# ble_emg_recorder_v11.net
KiCad netlist of a schematic drawn in EAGLE
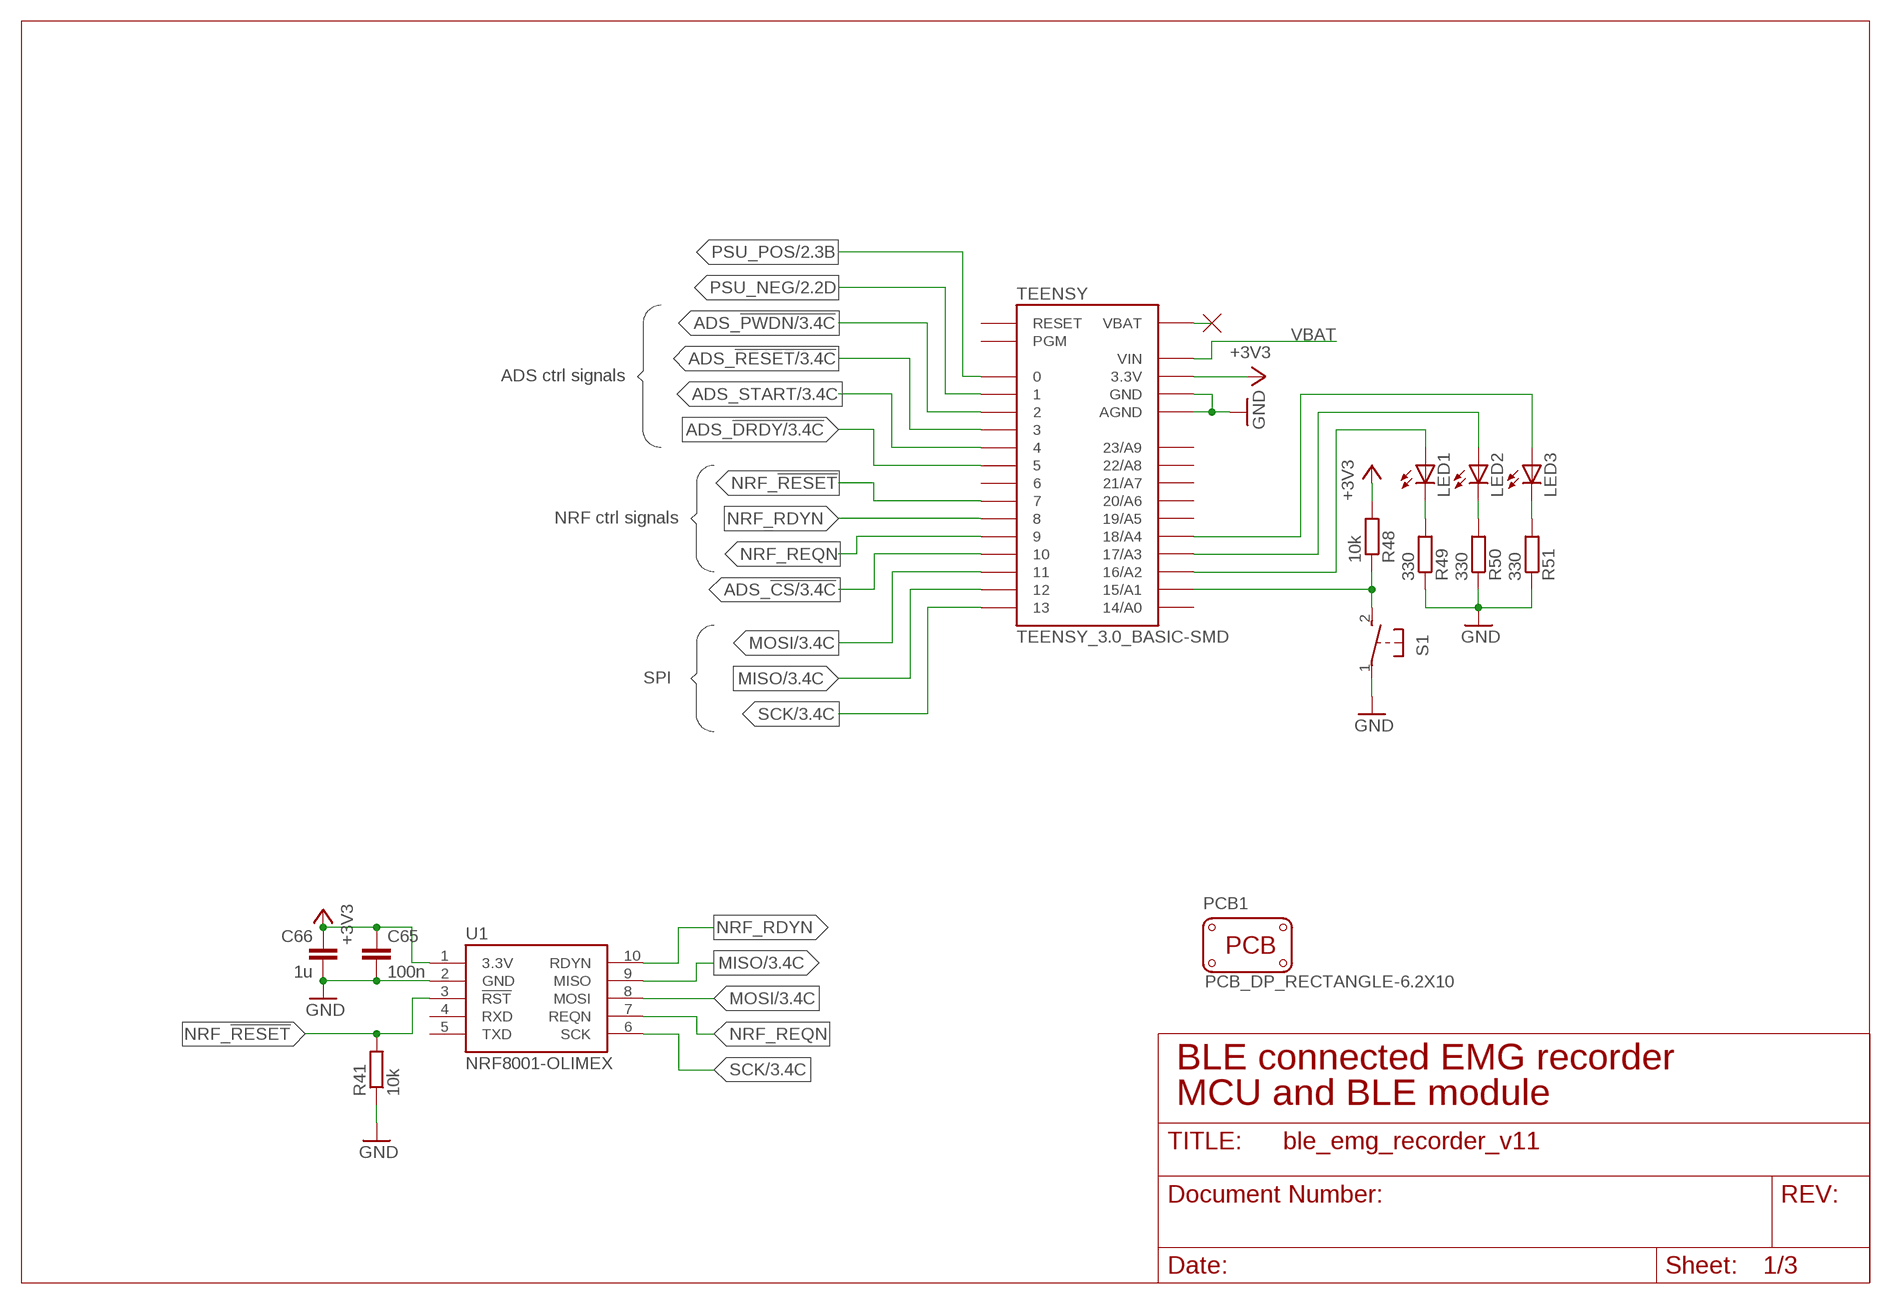
[diagram p0: schematic, sheet 1]
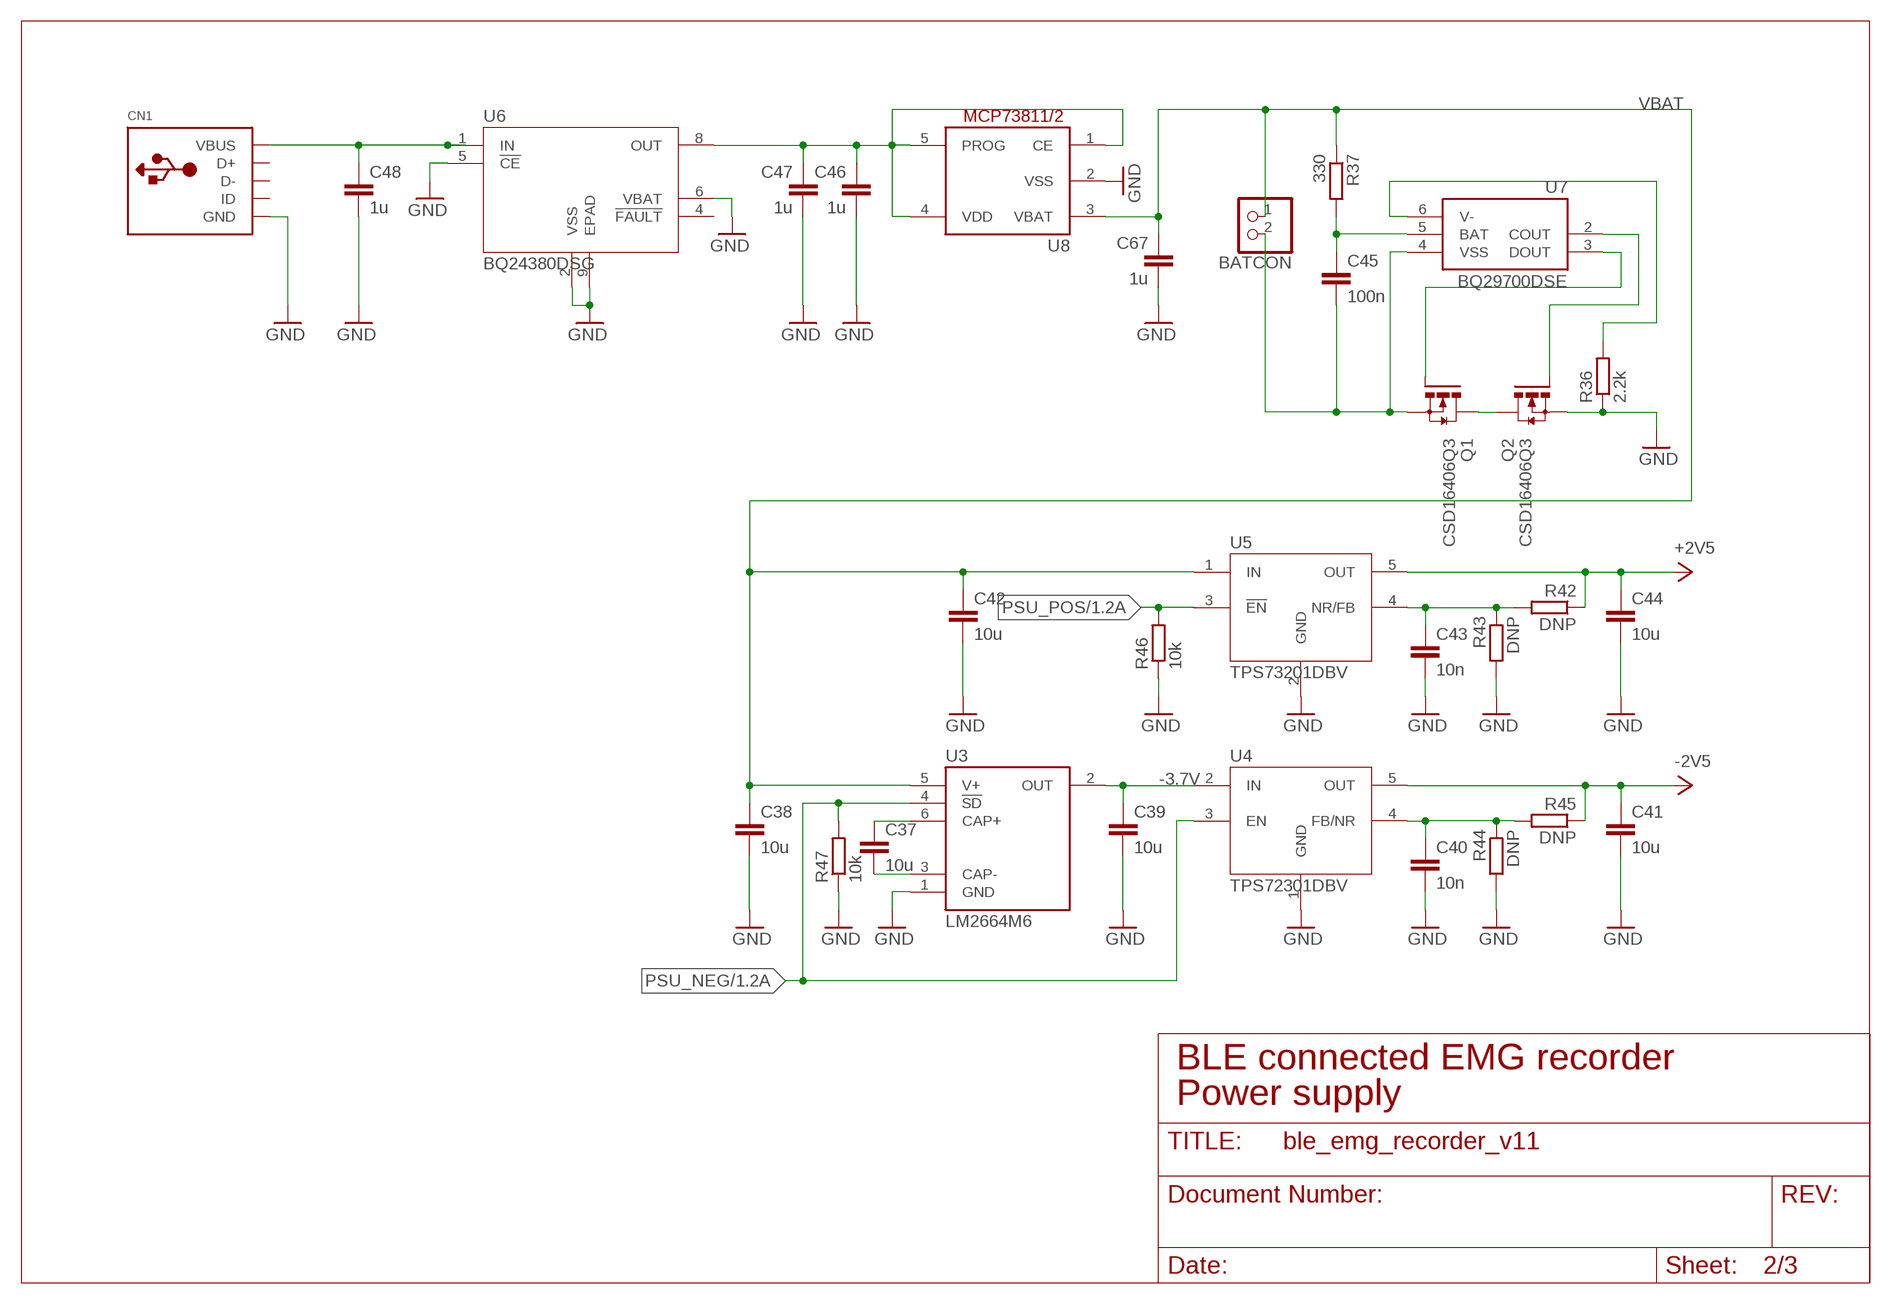
[diagram p1: schematic, sheet 2]
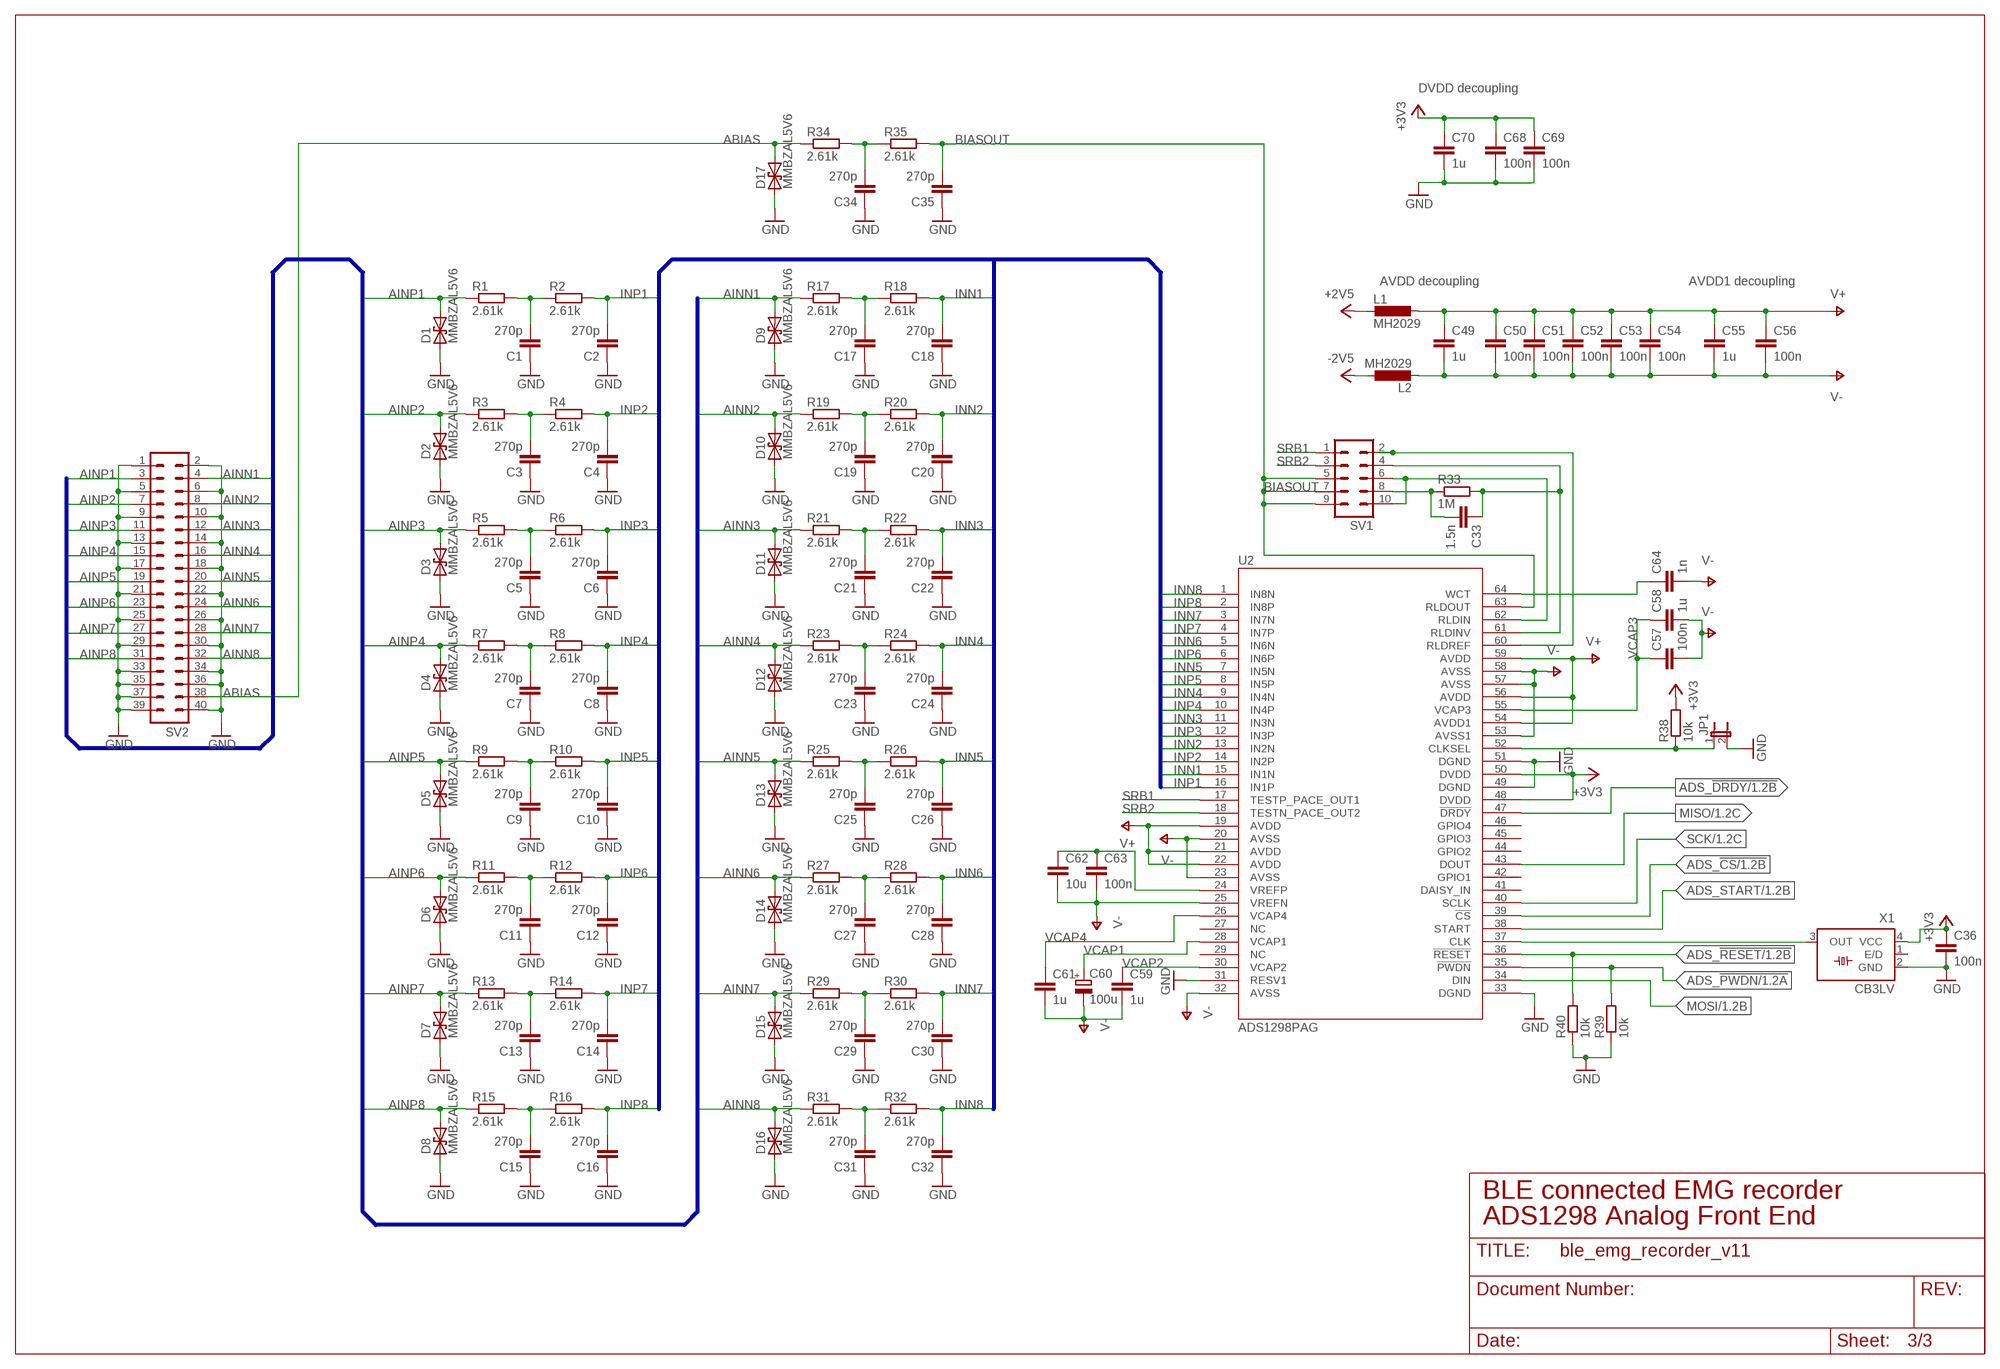
[diagram p2: schematic, sheet 3]

(export (version "E")
  (design (tool "Eeschema 10.0.6"))
  (components
    (comp (ref "C65")
      (value "100n")
      (footprint "eagle-import:C0805")
      (libsource (lib "eagle-import") (part "C-EUC0805"))
    )
    (comp (ref "C66")
      (value "1u")
      (footprint "eagle-import:C0805")
      (libsource (lib "eagle-import") (part "C-EUC0805"))
    )
    (comp (ref "LED1")
      (value "LEDCHIPLED_0805")
      (footprint "eagle-import:CHIPLED_0805")
      (libsource (lib "eagle-import") (part "LEDCHIPLED_0805"))
    )
    (comp (ref "LED2")
      (value "LEDCHIPLED_0805")
      (footprint "eagle-import:CHIPLED_0805")
      (libsource (lib "eagle-import") (part "LEDCHIPLED_0805"))
    )
    (comp (ref "LED3")
      (value "LEDCHIPLED_0805")
      (footprint "eagle-import:CHIPLED_0805")
      (libsource (lib "eagle-import") (part "LEDCHIPLED_0805"))
    )
    (comp (ref "PCB1")
      (value "PCB_DP_RECTANGLE-6.2X10")
      (footprint "eagle-import:DP10062_V1")
      (libsource (lib "eagle-import") (part "PCB_DP_RECTANGLE-6.2X10"))
    )
    (comp (ref "R41")
      (value "10k")
      (footprint "eagle-import:R0805")
      (libsource (lib "eagle-import") (part "R-EU_R0805"))
    )
    (comp (ref "R48")
      (value "10k")
      (footprint "eagle-import:R0805")
      (libsource (lib "eagle-import") (part "R-EU_R0805"))
    )
    (comp (ref "R49")
      (value "330")
      (footprint "eagle-import:R0805")
      (libsource (lib "eagle-import") (part "R-EU_R0805"))
    )
    (comp (ref "R50")
      (value "330")
      (footprint "eagle-import:R0805")
      (libsource (lib "eagle-import") (part "R-EU_R0805"))
    )
    (comp (ref "R51")
      (value "330")
      (footprint "eagle-import:R0805")
      (libsource (lib "eagle-import") (part "R-EU_R0805"))
    )
    (comp (ref "S1")
      (value "31-XX")
      (footprint "eagle-import:B3F-31XX")
      (fields (field (name "MPN") "B3F-3100"))
      (libsource (lib "eagle-import") (part "31-XX"))
    )
    (comp (ref "TEENSY")
      (value "TEENSY_3.0_BASIC-SMD")
      (footprint "eagle-import:TEENSY_3.0_BASIC-SMD")
      (libsource (lib "eagle-import") (part "TEENSY_3.0_BASIC-?SMD"))
    )
    (comp (ref "U1")
      (value "NRF8001-OLIMEX")
      (footprint "eagle-import:NRF8001-OLIMEX")
      (libsource (lib "eagle-import") (part "NRF8001-OLIMEX"))
    )
    (comp (ref "C1")
      (value "270p")
      (footprint "eagle-import:C0805")
      (libsource (lib "eagle-import") (part "C-EUC0805"))
    )
    (comp (ref "C2")
      (value "270p")
      (footprint "eagle-import:C0805")
      (fields (field (name "DIGIKEY") "1276-2494-1-ND"))
      (libsource (lib "eagle-import") (part "C-EUC0805"))
    )
    (comp (ref "C3")
      (value "270p")
      (footprint "eagle-import:C0805")
      (fields (field (name "DIGIKEY") "1276-2494-1-ND"))
      (libsource (lib "eagle-import") (part "C-EUC0805"))
    )
    (comp (ref "C4")
      (value "270p")
      (footprint "eagle-import:C0805")
      (fields (field (name "DIGIKEY") "1276-2494-1-ND"))
      (libsource (lib "eagle-import") (part "C-EUC0805"))
    )
    (comp (ref "C5")
      (value "270p")
      (footprint "eagle-import:C0805")
      (fields (field (name "DIGIKEY") "1276-2494-1-ND"))
      (libsource (lib "eagle-import") (part "C-EUC0805"))
    )
    (comp (ref "C6")
      (value "270p")
      (footprint "eagle-import:C0805")
      (fields (field (name "DIGIKEY") "1276-2494-1-ND"))
      (libsource (lib "eagle-import") (part "C-EUC0805"))
    )
    (comp (ref "C7")
      (value "270p")
      (footprint "eagle-import:C0805")
      (fields (field (name "DIGIKEY") "1276-2494-1-ND"))
      (libsource (lib "eagle-import") (part "C-EUC0805"))
    )
    (comp (ref "C8")
      (value "270p")
      (footprint "eagle-import:C0805")
      (fields (field (name "DIGIKEY") "1276-2494-1-ND"))
      (libsource (lib "eagle-import") (part "C-EUC0805"))
    )
    (comp (ref "C9")
      (value "270p")
      (footprint "eagle-import:C0805")
      (fields (field (name "DIGIKEY") "1276-2494-1-ND"))
      (libsource (lib "eagle-import") (part "C-EUC0805"))
    )
    (comp (ref "C10")
      (value "270p")
      (footprint "eagle-import:C0805")
      (fields (field (name "DIGIKEY") "1276-2494-1-ND"))
      (libsource (lib "eagle-import") (part "C-EUC0805"))
    )
    (comp (ref "C11")
      (value "270p")
      (footprint "eagle-import:C0805")
      (fields (field (name "DIGIKEY") "1276-2494-1-ND"))
      (libsource (lib "eagle-import") (part "C-EUC0805"))
    )
    (comp (ref "C12")
      (value "270p")
      (footprint "eagle-import:C0805")
      (fields (field (name "DIGIKEY") "1276-2494-1-ND"))
      (libsource (lib "eagle-import") (part "C-EUC0805"))
    )
    (comp (ref "C13")
      (value "270p")
      (footprint "eagle-import:C0805")
      (fields (field (name "DIGIKEY") "1276-2494-1-ND"))
      (libsource (lib "eagle-import") (part "C-EUC0805"))
    )
    (comp (ref "C14")
      (value "270p")
      (footprint "eagle-import:C0805")
      (fields (field (name "DIGIKEY") "1276-2494-1-ND"))
      (libsource (lib "eagle-import") (part "C-EUC0805"))
    )
    (comp (ref "C15")
      (value "270p")
      (footprint "eagle-import:C0805")
      (fields (field (name "DIGIKEY") "1276-2494-1-ND"))
      (libsource (lib "eagle-import") (part "C-EUC0805"))
    )
    (comp (ref "C16")
      (value "270p")
      (footprint "eagle-import:C0805")
      (fields (field (name "DIGIKEY") "1276-2494-1-ND"))
      (libsource (lib "eagle-import") (part "C-EUC0805"))
    )
    (comp (ref "C17")
      (value "270p")
      (footprint "eagle-import:C0805")
      (fields (field (name "DIGIKEY") "1276-2494-1-ND"))
      (libsource (lib "eagle-import") (part "C-EUC0805"))
    )
    (comp (ref "C18")
      (value "270p")
      (footprint "eagle-import:C0805")
      (fields (field (name "DIGIKEY") "1276-2494-1-ND"))
      (libsource (lib "eagle-import") (part "C-EUC0805"))
    )
    (comp (ref "C19")
      (value "270p")
      (footprint "eagle-import:C0805")
      (fields (field (name "DIGIKEY") "1276-2494-1-ND"))
      (libsource (lib "eagle-import") (part "C-EUC0805"))
    )
    (comp (ref "C20")
      (value "270p")
      (footprint "eagle-import:C0805")
      (fields (field (name "DIGIKEY") "1276-2494-1-ND"))
      (libsource (lib "eagle-import") (part "C-EUC0805"))
    )
    (comp (ref "C21")
      (value "270p")
      (footprint "eagle-import:C0805")
      (fields (field (name "DIGIKEY") "1276-2494-1-ND"))
      (libsource (lib "eagle-import") (part "C-EUC0805"))
    )
    (comp (ref "C22")
      (value "270p")
      (footprint "eagle-import:C0805")
      (fields (field (name "DIGIKEY") "1276-2494-1-ND"))
      (libsource (lib "eagle-import") (part "C-EUC0805"))
    )
    (comp (ref "C23")
      (value "270p")
      (footprint "eagle-import:C0805")
      (fields (field (name "DIGIKEY") "1276-2494-1-ND"))
      (libsource (lib "eagle-import") (part "C-EUC0805"))
    )
    (comp (ref "C24")
      (value "270p")
      (footprint "eagle-import:C0805")
      (fields (field (name "DIGIKEY") "1276-2494-1-ND"))
      (libsource (lib "eagle-import") (part "C-EUC0805"))
    )
    (comp (ref "C25")
      (value "270p")
      (footprint "eagle-import:C0805")
      (fields (field (name "DIGIKEY") "1276-2494-1-ND"))
      (libsource (lib "eagle-import") (part "C-EUC0805"))
    )
    (comp (ref "C26")
      (value "270p")
      (footprint "eagle-import:C0805")
      (fields (field (name "DIGIKEY") "1276-2494-1-ND"))
      (libsource (lib "eagle-import") (part "C-EUC0805"))
    )
    (comp (ref "C27")
      (value "270p")
      (footprint "eagle-import:C0805")
      (fields (field (name "DIGIKEY") "1276-2494-1-ND"))
      (libsource (lib "eagle-import") (part "C-EUC0805"))
    )
    (comp (ref "C28")
      (value "270p")
      (footprint "eagle-import:C0805")
      (fields (field (name "DIGIKEY") "1276-2494-1-ND"))
      (libsource (lib "eagle-import") (part "C-EUC0805"))
    )
    (comp (ref "C29")
      (value "270p")
      (footprint "eagle-import:C0805")
      (fields (field (name "DIGIKEY") "1276-2494-1-ND"))
      (libsource (lib "eagle-import") (part "C-EUC0805"))
    )
    (comp (ref "C30")
      (value "270p")
      (footprint "eagle-import:C0805")
      (fields (field (name "DIGIKEY") "1276-2494-1-ND"))
      (libsource (lib "eagle-import") (part "C-EUC0805"))
    )
    (comp (ref "C31")
      (value "270p")
      (footprint "eagle-import:C0805")
      (fields (field (name "DIGIKEY") "1276-2494-1-ND"))
      (libsource (lib "eagle-import") (part "C-EUC0805"))
    )
    (comp (ref "C32")
      (value "270p")
      (footprint "eagle-import:C0805")
      (fields (field (name "DIGIKEY") "1276-2494-1-ND"))
      (libsource (lib "eagle-import") (part "C-EUC0805"))
    )
    (comp (ref "C33")
      (value "1.5n")
      (footprint "eagle-import:C0805")
      (libsource (lib "eagle-import") (part "C-EUC0805"))
    )
    (comp (ref "C34")
      (value "270p")
      (footprint "eagle-import:C0805")
      (fields (field (name "DIGIKEY") "1276-2494-1-ND"))
      (libsource (lib "eagle-import") (part "C-EUC0805"))
    )
    (comp (ref "C35")
      (value "270p")
      (footprint "eagle-import:C0805")
      (fields (field (name "DIGIKEY") "1276-2494-1-ND"))
      (libsource (lib "eagle-import") (part "C-EUC0805"))
    )
    (comp (ref "C36")
      (value "100n")
      (footprint "eagle-import:C0805")
      (libsource (lib "eagle-import") (part "C-EUC0805"))
    )
    (comp (ref "C49")
      (value "1u")
      (footprint "eagle-import:C0805")
      (libsource (lib "eagle-import") (part "C-EUC0805"))
    )
    (comp (ref "C50")
      (value "100n")
      (footprint "eagle-import:C0402")
      (libsource (lib "eagle-import") (part "C-EUC0402"))
    )
    (comp (ref "C51")
      (value "100n")
      (footprint "eagle-import:C0402")
      (libsource (lib "eagle-import") (part "C-EUC0402"))
    )
    (comp (ref "C52")
      (value "100n")
      (footprint "eagle-import:C0402")
      (libsource (lib "eagle-import") (part "C-EUC0402"))
    )
    (comp (ref "C53")
      (value "100n")
      (footprint "eagle-import:C0402")
      (libsource (lib "eagle-import") (part "C-EUC0402"))
    )
    (comp (ref "C54")
      (value "100n")
      (footprint "eagle-import:C0402")
      (libsource (lib "eagle-import") (part "C-EUC0402"))
    )
    (comp (ref "C55")
      (value "1u")
      (footprint "eagle-import:C0805")
      (libsource (lib "eagle-import") (part "C-EUC0805"))
    )
    (comp (ref "C56")
      (value "100n")
      (footprint "eagle-import:C0402")
      (libsource (lib "eagle-import") (part "C-EUC0402"))
    )
    (comp (ref "C57")
      (value "100n")
      (footprint "eagle-import:C0402")
      (libsource (lib "eagle-import") (part "C-EUC0402"))
    )
    (comp (ref "C58")
      (value "1u")
      (footprint "eagle-import:C0805")
      (libsource (lib "eagle-import") (part "C-EUC0805"))
    )
    (comp (ref "C59")
      (value "1u")
      (footprint "eagle-import:C0805")
      (libsource (lib "eagle-import") (part "C-EUC0805"))
    )
    (comp (ref "C60")
      (value "100u")
      (footprint "eagle-import:D_7343-31W")
      (libsource (lib "eagle-import") (part "CPOL-EUD/7343-31W"))
    )
    (comp (ref "C61")
      (value "1u")
      (footprint "eagle-import:C0805")
      (libsource (lib "eagle-import") (part "C-EUC0805"))
    )
    (comp (ref "C62")
      (value "10u")
      (footprint "eagle-import:C0805")
      (libsource (lib "eagle-import") (part "C-EUC0805"))
    )
    (comp (ref "C63")
      (value "100n")
      (footprint "eagle-import:C0402")
      (libsource (lib "eagle-import") (part "C-EUC0402"))
    )
    (comp (ref "C64")
      (value "1n")
      (footprint "eagle-import:C0402")
      (libsource (lib "eagle-import") (part "C-EUC0402"))
    )
    (comp (ref "C68")
      (value "100n")
      (footprint "eagle-import:C0402")
      (libsource (lib "eagle-import") (part "C-EUC0402"))
    )
    (comp (ref "C69")
      (value "100n")
      (footprint "eagle-import:C0402")
      (libsource (lib "eagle-import") (part "C-EUC0402"))
    )
    (comp (ref "C70")
      (value "1u")
      (footprint "eagle-import:C0805")
      (libsource (lib "eagle-import") (part "C-EUC0805"))
    )
    (comp (ref "D1")
      (value "MMBZAL5V6")
      (footprint "eagle-import:SOT23")
      (libsource (lib "eagle-import") (part "MMBZ?AL5V6"))
    )
    (comp (ref "D2")
      (value "MMBZAL5V6")
      (footprint "eagle-import:SOT23")
      (libsource (lib "eagle-import") (part "MMBZ?AL5V6"))
    )
    (comp (ref "D3")
      (value "MMBZAL5V6")
      (footprint "eagle-import:SOT23")
      (libsource (lib "eagle-import") (part "MMBZ?AL5V6"))
    )
    (comp (ref "D4")
      (value "MMBZAL5V6")
      (footprint "eagle-import:SOT23")
      (libsource (lib "eagle-import") (part "MMBZ?AL5V6"))
    )
    (comp (ref "D5")
      (value "MMBZAL5V6")
      (footprint "eagle-import:SOT23")
      (libsource (lib "eagle-import") (part "MMBZ?AL5V6"))
    )
    (comp (ref "D6")
      (value "MMBZAL5V6")
      (footprint "eagle-import:SOT23")
      (libsource (lib "eagle-import") (part "MMBZ?AL5V6"))
    )
    (comp (ref "D7")
      (value "MMBZAL5V6")
      (footprint "eagle-import:SOT23")
      (libsource (lib "eagle-import") (part "MMBZ?AL5V6"))
    )
    (comp (ref "D8")
      (value "MMBZAL5V6")
      (footprint "eagle-import:SOT23")
      (libsource (lib "eagle-import") (part "MMBZ?AL5V6"))
    )
    (comp (ref "D9")
      (value "MMBZAL5V6")
      (footprint "eagle-import:SOT23")
      (libsource (lib "eagle-import") (part "MMBZ?AL5V6"))
    )
    (comp (ref "D10")
      (value "MMBZAL5V6")
      (footprint "eagle-import:SOT23")
      (libsource (lib "eagle-import") (part "MMBZ?AL5V6"))
    )
    (comp (ref "D11")
      (value "MMBZAL5V6")
      (footprint "eagle-import:SOT23")
      (libsource (lib "eagle-import") (part "MMBZ?AL5V6"))
    )
    (comp (ref "D12")
      (value "MMBZAL5V6")
      (footprint "eagle-import:SOT23")
      (libsource (lib "eagle-import") (part "MMBZ?AL5V6"))
    )
    (comp (ref "D13")
      (value "MMBZAL5V6")
      (footprint "eagle-import:SOT23")
      (libsource (lib "eagle-import") (part "MMBZ?AL5V6"))
    )
    (comp (ref "D14")
      (value "MMBZAL5V6")
      (footprint "eagle-import:SOT23")
      (libsource (lib "eagle-import") (part "MMBZ?AL5V6"))
    )
    (comp (ref "D15")
      (value "MMBZAL5V6")
      (footprint "eagle-import:SOT23")
      (libsource (lib "eagle-import") (part "MMBZ?AL5V6"))
    )
    (comp (ref "D16")
      (value "MMBZAL5V6")
      (footprint "eagle-import:SOT23")
      (libsource (lib "eagle-import") (part "MMBZ?AL5V6"))
    )
    (comp (ref "D17")
      (value "MMBZAL5V6")
      (footprint "eagle-import:SOT23")
      (libsource (lib "eagle-import") (part "MMBZ?AL5V6"))
    )
    (comp (ref "JP1")
      (value "JP1E")
      (footprint "eagle-import:JP1")
      (libsource (lib "eagle-import") (part "JP1E"))
    )
    (comp (ref "L1")
      (value "MH2029")
      (footprint "eagle-import:L0805")
      (libsource (lib "eagle-import") (part "FERRITE-FILTER"))
    )
    (comp (ref "L2")
      (value "MH2029")
      (footprint "eagle-import:L0805")
      (libsource (lib "eagle-import") (part "FERRITE-FILTER"))
    )
    (comp (ref "R1")
      (value "2.61k")
      (footprint "eagle-import:R0805")
      (fields (field (name "DIGIKEY") "RMCF0805FT2K61CT-ND"))
      (libsource (lib "eagle-import") (part "R-EU_R0805"))
    )
    (comp (ref "R2")
      (value "2.61k")
      (footprint "eagle-import:R0805")
      (fields (field (name "DIGIKEY") "RMCF0805FT2K61CT-ND"))
      (libsource (lib "eagle-import") (part "R-EU_R0805"))
    )
    (comp (ref "R3")
      (value "2.61k")
      (footprint "eagle-import:R0805")
      (fields (field (name "DIGIKEY") "RMCF0805FT2K61CT-ND"))
      (libsource (lib "eagle-import") (part "R-EU_R0805"))
    )
    (comp (ref "R4")
      (value "2.61k")
      (footprint "eagle-import:R0805")
      (fields (field (name "DIGIKEY") "RMCF0805FT2K61CT-ND"))
      (libsource (lib "eagle-import") (part "R-EU_R0805"))
    )
    (comp (ref "R5")
      (value "2.61k")
      (footprint "eagle-import:R0805")
      (fields (field (name "DIGIKEY") "RMCF0805FT2K61CT-ND"))
      (libsource (lib "eagle-import") (part "R-EU_R0805"))
    )
    (comp (ref "R6")
      (value "2.61k")
      (footprint "eagle-import:R0805")
      (fields (field (name "DIGIKEY") "RMCF0805FT2K61CT-ND"))
      (libsource (lib "eagle-import") (part "R-EU_R0805"))
    )
    (comp (ref "R7")
      (value "2.61k")
      (footprint "eagle-import:R0805")
      (fields (field (name "DIGIKEY") "RMCF0805FT2K61CT-ND"))
      (libsource (lib "eagle-import") (part "R-EU_R0805"))
    )
    (comp (ref "R8")
      (value "2.61k")
      (footprint "eagle-import:R0805")
      (fields (field (name "DIGIKEY") "RMCF0805FT2K61CT-ND"))
      (libsource (lib "eagle-import") (part "R-EU_R0805"))
    )
    (comp (ref "R9")
      (value "2.61k")
      (footprint "eagle-import:R0805")
      (fields (field (name "DIGIKEY") "RMCF0805FT2K61CT-ND"))
      (libsource (lib "eagle-import") (part "R-EU_R0805"))
    )
    (comp (ref "R10")
      (value "2.61k")
      (footprint "eagle-import:R0805")
      (fields (field (name "DIGIKEY") "RMCF0805FT2K61CT-ND"))
      (libsource (lib "eagle-import") (part "R-EU_R0805"))
    )
    (comp (ref "R11")
      (value "2.61k")
      (footprint "eagle-import:R0805")
      (fields (field (name "DIGIKEY") "RMCF0805FT2K61CT-ND"))
      (libsource (lib "eagle-import") (part "R-EU_R0805"))
    )
    (comp (ref "R12")
      (value "2.61k")
      (footprint "eagle-import:R0805")
      (fields (field (name "DIGIKEY") "RMCF0805FT2K61CT-ND"))
      (libsource (lib "eagle-import") (part "R-EU_R0805"))
    )
    (comp (ref "R13")
      (value "2.61k")
      (footprint "eagle-import:R0805")
      (fields (field (name "DIGIKEY") "RMCF0805FT2K61CT-ND"))
      (libsource (lib "eagle-import") (part "R-EU_R0805"))
    )
    (comp (ref "R14")
      (value "2.61k")
      (footprint "eagle-import:R0805")
      (fields (field (name "DIGIKEY") "RMCF0805FT2K61CT-ND"))
      (libsource (lib "eagle-import") (part "R-EU_R0805"))
    )
    (comp (ref "R15")
      (value "2.61k")
      (footprint "eagle-import:R0805")
      (fields (field (name "DIGIKEY") "RMCF0805FT2K61CT-ND"))
      (libsource (lib "eagle-import") (part "R-EU_R0805"))
    )
    (comp (ref "R16")
      (value "2.61k")
      (footprint "eagle-import:R0805")
      (fields (field (name "DIGIKEY") "RMCF0805FT2K61CT-ND"))
      (libsource (lib "eagle-import") (part "R-EU_R0805"))
    )
    (comp (ref "R17")
      (value "2.61k")
      (footprint "eagle-import:R0805")
      (fields (field (name "DIGIKEY") "RMCF0805FT2K61CT-ND"))
      (libsource (lib "eagle-import") (part "R-EU_R0805"))
    )
    (comp (ref "R18")
      (value "2.61k")
      (footprint "eagle-import:R0805")
      (fields (field (name "DIGIKEY") "RMCF0805FT2K61CT-ND"))
      (libsource (lib "eagle-import") (part "R-EU_R0805"))
    )
    (comp (ref "R19")
      (value "2.61k")
      (footprint "eagle-import:R0805")
      (fields (field (name "DIGIKEY") "RMCF0805FT2K61CT-ND"))
      (libsource (lib "eagle-import") (part "R-EU_R0805"))
    )
    (comp (ref "R20")
      (value "2.61k")
      (footprint "eagle-import:R0805")
      (fields (field (name "DIGIKEY") "RMCF0805FT2K61CT-ND"))
      (libsource (lib "eagle-import") (part "R-EU_R0805"))
    )
    (comp (ref "R21")
      (value "2.61k")
      (footprint "eagle-import:R0805")
      (fields (field (name "DIGIKEY") "RMCF0805FT2K61CT-ND"))
      (libsource (lib "eagle-import") (part "R-EU_R0805"))
    )
    (comp (ref "R22")
      (value "2.61k")
      (footprint "eagle-import:R0805")
      (fields (field (name "DIGIKEY") "RMCF0805FT2K61CT-ND"))
      (libsource (lib "eagle-import") (part "R-EU_R0805"))
    )
    (comp (ref "R23")
      (value "2.61k")
      (footprint "eagle-import:R0805")
      (fields (field (name "DIGIKEY") "RMCF0805FT2K61CT-ND"))
      (libsource (lib "eagle-import") (part "R-EU_R0805"))
    )
    (comp (ref "R24")
      (value "2.61k")
      (footprint "eagle-import:R0805")
      (fields (field (name "DIGIKEY") "RMCF0805FT2K61CT-ND"))
      (libsource (lib "eagle-import") (part "R-EU_R0805"))
    )
    (comp (ref "R25")
      (value "2.61k")
      (footprint "eagle-import:R0805")
      (fields (field (name "DIGIKEY") "RMCF0805FT2K61CT-ND"))
      (libsource (lib "eagle-import") (part "R-EU_R0805"))
    )
    (comp (ref "R26")
      (value "2.61k")
      (footprint "eagle-import:R0805")
      (fields (field (name "DIGIKEY") "RMCF0805FT2K61CT-ND"))
      (libsource (lib "eagle-import") (part "R-EU_R0805"))
    )
    (comp (ref "R27")
      (value "2.61k")
      (footprint "eagle-import:R0805")
      (fields (field (name "DIGIKEY") "RMCF0805FT2K61CT-ND"))
      (libsource (lib "eagle-import") (part "R-EU_R0805"))
    )
    (comp (ref "R28")
      (value "2.61k")
      (footprint "eagle-import:R0805")
      (fields (field (name "DIGIKEY") "RMCF0805FT2K61CT-ND"))
      (libsource (lib "eagle-import") (part "R-EU_R0805"))
    )
    (comp (ref "R29")
      (value "2.61k")
      (footprint "eagle-import:R0805")
      (fields (field (name "DIGIKEY") "RMCF0805FT2K61CT-ND"))
      (libsource (lib "eagle-import") (part "R-EU_R0805"))
    )
    (comp (ref "R30")
      (value "2.61k")
      (footprint "eagle-import:R0805")
      (fields (field (name "DIGIKEY") "RMCF0805FT2K61CT-ND"))
      (libsource (lib "eagle-import") (part "R-EU_R0805"))
    )
    (comp (ref "R31")
      (value "2.61k")
      (footprint "eagle-import:R0805")
      (fields (field (name "DIGIKEY") "RMCF0805FT2K61CT-ND"))
      (libsource (lib "eagle-import") (part "R-EU_R0805"))
    )
    (comp (ref "R32")
      (value "2.61k")
      (footprint "eagle-import:R0805")
      (fields (field (name "DIGIKEY") "RMCF0805FT2K61CT-ND"))
      (libsource (lib "eagle-import") (part "R-EU_R0805"))
    )
    (comp (ref "R33")
      (value "1M")
      (footprint "eagle-import:R0805")
      (libsource (lib "eagle-import") (part "R-EU_R0805"))
    )
    (comp (ref "R34")
      (value "2.61k")
      (footprint "eagle-import:R0805")
      (fields (field (name "DIGIKEY") "RMCF0805FT2K61CT-ND"))
      (libsource (lib "eagle-import") (part "R-EU_R0805"))
    )
    (comp (ref "R35")
      (value "2.61k")
      (footprint "eagle-import:R0805")
      (fields (field (name "DIGIKEY") "RMCF0805FT2K61CT-ND"))
      (libsource (lib "eagle-import") (part "R-EU_R0805"))
    )
    (comp (ref "R38")
      (value "10k")
      (footprint "eagle-import:R0805")
      (libsource (lib "eagle-import") (part "R-EU_R0805"))
    )
    (comp (ref "R39")
      (value "10k")
      (footprint "eagle-import:R0805")
      (libsource (lib "eagle-import") (part "R-EU_R0805"))
    )
    (comp (ref "R40")
      (value "10k")
      (footprint "eagle-import:R0805")
      (libsource (lib "eagle-import") (part "R-EU_R0805"))
    )
    (comp (ref "SV1")
      (value "MA05-2")
      (footprint "eagle-import:MA05-2")
      (libsource (lib "eagle-import") (part "MA05-2"))
    )
    (comp (ref "SV2")
      (value "ML40")
      (footprint "eagle-import:ML40")
      (libsource (lib "eagle-import") (part "ML40"))
    )
    (comp (ref "U2")
      (value "ADS1298PAG")
      (footprint "eagle-import:PAG64")
      (fields
        (field (name "GENERIC_PART_NUMBER") "ADS1298")
        (field (name "MANUFACTURER") "Texas Instruments")
      )
      (libsource (lib "eagle-import") (part "ADS1298PAG"))
    )
    (comp (ref "X1")
      (value "CB3LV")
      (footprint "eagle-import:SM77H")
      (libsource (lib "eagle-import") (part "SM77H"))
    )
    (comp (ref "BATCON")
      (value "JST_2PIN-THM-RA")
      (footprint "eagle-import:JST-PH-2-THM-RA")
      (libsource (lib "eagle-import") (part "JST_2PIN-THM-RA"))
    )
    (comp (ref "C37")
      (value "10u")
      (footprint "eagle-import:C0805")
      (libsource (lib "eagle-import") (part "C-EUC0805"))
    )
    (comp (ref "C38")
      (value "10u")
      (footprint "eagle-import:C0805")
      (libsource (lib "eagle-import") (part "C-EUC0805"))
    )
    (comp (ref "C39")
      (value "10u")
      (footprint "eagle-import:C0805")
      (libsource (lib "eagle-import") (part "C-EUC0805"))
    )
    (comp (ref "C40")
      (value "10n")
      (footprint "eagle-import:C0805")
      (libsource (lib "eagle-import") (part "C-EUC0805"))
    )
    (comp (ref "C41")
      (value "10u")
      (footprint "eagle-import:C0805")
      (libsource (lib "eagle-import") (part "C-EUC0805"))
    )
    (comp (ref "C42")
      (value "10u")
      (footprint "eagle-import:C0805")
      (libsource (lib "eagle-import") (part "C-EUC0805"))
    )
    (comp (ref "C43")
      (value "10n")
      (footprint "eagle-import:C0805")
      (libsource (lib "eagle-import") (part "C-EUC0805"))
    )
    (comp (ref "C44")
      (value "10u")
      (footprint "eagle-import:C0805")
      (libsource (lib "eagle-import") (part "C-EUC0805"))
    )
    (comp (ref "C45")
      (value "100n")
      (footprint "eagle-import:C0805")
      (libsource (lib "eagle-import") (part "C-EUC0805"))
    )
    (comp (ref "C46")
      (value "1u")
      (footprint "eagle-import:C0805")
      (libsource (lib "eagle-import") (part "C-EUC0805"))
    )
    (comp (ref "C47")
      (value "1u")
      (footprint "eagle-import:C0805")
      (libsource (lib "eagle-import") (part "C-EUC0805"))
    )
    (comp (ref "C48")
      (value "1u")
      (footprint "eagle-import:C0805")
      (libsource (lib "eagle-import") (part "C-EUC0805"))
    )
    (comp (ref "C67")
      (value "1u")
      (footprint "eagle-import:C0805")
      (libsource (lib "eagle-import") (part "C-EUC0805"))
    )
    (comp (ref "CN1")
      (value "USBMINIB")
      (footprint "eagle-import:USB-MINIB")
      (libsource (lib "eagle-import") (part "USBMINIB"))
    )
    (comp (ref "Q1")
      (value "CSD16406Q3")
      (footprint "eagle-import:DQV8-L")
      (libsource (lib "eagle-import") (part "CSD16406Q3"))
    )
    (comp (ref "Q2")
      (value "CSD16406Q3")
      (footprint "eagle-import:DQV8-L")
      (libsource (lib "eagle-import") (part "CSD16406Q3"))
    )
    (comp (ref "R36")
      (value "2.2k")
      (footprint "eagle-import:R0805")
      (libsource (lib "eagle-import") (part "R-EU_R0805"))
    )
    (comp (ref "R37")
      (value "330")
      (footprint "eagle-import:R0805")
      (libsource (lib "eagle-import") (part "R-EU_R0805"))
    )
    (comp (ref "R42")
      (value "DNP")
      (footprint "eagle-import:R0805")
      (libsource (lib "eagle-import") (part "R-EU_R0805"))
    )
    (comp (ref "R43")
      (value "DNP")
      (footprint "eagle-import:R0805")
      (libsource (lib "eagle-import") (part "R-EU_R0805"))
    )
    (comp (ref "R44")
      (value "DNP")
      (footprint "eagle-import:R0805")
      (libsource (lib "eagle-import") (part "R-EU_R0805"))
    )
    (comp (ref "R45")
      (value "DNP")
      (footprint "eagle-import:R0805")
      (libsource (lib "eagle-import") (part "R-EU_R0805"))
    )
    (comp (ref "R46")
      (value "10k")
      (footprint "eagle-import:R0805")
      (libsource (lib "eagle-import") (part "R-EU_R0805"))
    )
    (comp (ref "R47")
      (value "10k")
      (footprint "eagle-import:R0805")
      (libsource (lib "eagle-import") (part "R-EU_R0805"))
    )
    (comp (ref "U3")
      (value "LM2664M6")
      (footprint "eagle-import:SOT95P300X120-6N")
      (libsource (lib "eagle-import") (part "LM2664M6"))
    )
    (comp (ref "U4")
      (value "TPS72301DBV")
      (footprint "eagle-import:DBV5")
      (fields
        (field (name "GENERIC_PART_NUMBER") "TPS72301")
        (field (name "MANUFACTURER") "Texas Instruments")
        (field (name "MANUFACTURER_PART_NUMBER") "tps72301_dbv_5")
      )
      (libsource (lib "eagle-import") (part "TPS72301DBV"))
    )
    (comp (ref "U5")
      (value "TPS73201DBV")
      (footprint "eagle-import:DBV5")
      (fields
        (field (name "GENERIC_PART_NUMBER") "TPS73201")
        (field (name "MANUFACTURER") "Texas Instruments")
        (field (name "MANUFACTURER_PART_NUMBER") "tps73201_dbv_5")
      )
      (libsource (lib "eagle-import") (part "TPS73201DBV"))
    )
    (comp (ref "U6")
      (value "BQ24380DSG")
      (footprint "eagle-import:DSG8_P9X1P6")
      (fields
        (field (name "GENERIC_PART_NUMBER") "BQ24380")
        (field (name "MANUFACTURER") "Texas Instruments")
      )
      (libsource (lib "eagle-import") (part "BQ24380DSG"))
    )
    (comp (ref "U7")
      (value "BQ29700DSE")
      (footprint "eagle-import:DSE6")
      (libsource (lib "eagle-import") (part "BQ29700DSE"))
    )
    (comp (ref "U8")
      (value "MCP73811/2")
      (footprint "eagle-import:SOT23-5L")
      (libsource (lib "eagle-import") (part "MCP73811/2"))
    )
  )
  (nets
    (net (code "1") (name "+2V5") (class "Default")
      (node (ref "C44") (pin "1") (pinfunction "1_1") (pintype "passive"))
      (node (ref "L1") (pin "2") (pinfunction "2_2") (pintype "passive"))
      (node (ref "R42") (pin "1") (pinfunction "1_1") (pintype "passive"))
      (node (ref "U5") (pin "5") (pinfunction "OUT_5") (pintype "output"))
    )
    (net (code "2") (name "+3V3") (class "Default")
      (node (ref "C36") (pin "1") (pinfunction "1_1") (pintype "passive"))
      (node (ref "C65") (pin "1") (pinfunction "1_1") (pintype "passive"))
      (node (ref "C66") (pin "1") (pinfunction "1_1") (pintype "passive"))
      (node (ref "C68") (pin "1") (pinfunction "1_1") (pintype "passive"))
      (node (ref "C69") (pin "1") (pinfunction "1_1") (pintype "passive"))
      (node (ref "C70") (pin "1") (pinfunction "1_1") (pintype "passive"))
      (node (ref "R38") (pin "2") (pinfunction "2_2") (pintype "passive"))
      (node (ref "R48") (pin "2") (pinfunction "2_2") (pintype "passive"))
      (node (ref "TEENSY") (pin "3.3V") (pinfunction "3.3V_3.3V") (pintype "power_in"))
      (node (ref "TEENSY") (pin "3.3V1") (pinfunction "3.3V_3.3V1") (pintype "power_in"))
      (node (ref "U1") (pin "1") (pinfunction "3.3V_1") (pintype "power_in"))
      (node (ref "U2") (pin "48") (pinfunction "DVDD_48") (pintype "power_in"))
      (node (ref "U2") (pin "50") (pinfunction "DVDD_50") (pintype "power_in"))
      (node (ref "X1") (pin "4") (pinfunction "VCC_4") (pintype "power_in"))
    )
    (net (code "3") (name "-2V5") (class "Default")
      (node (ref "C41") (pin "1") (pinfunction "1_1") (pintype "passive"))
      (node (ref "L2") (pin "1") (pinfunction "1_1") (pintype "passive"))
      (node (ref "R45") (pin "1") (pinfunction "1_1") (pintype "passive"))
      (node (ref "U4") (pin "5") (pinfunction "OUT_5") (pintype "output"))
    )
    (net (code "4") (name "ABIAS") (class "Default")
      (node (ref "D17") (pin "2") (pinfunction "2_2") (pintype "passive"))
      (node (ref "R34") (pin "1") (pinfunction "1_1") (pintype "passive"))
      (node (ref "SV2") (pin "38") (pinfunction "38_38") (pintype "passive"))
    )
    (net (code "5") (name "ADS_START") (class "Default")
      (node (ref "TEENSY") (pin "4") (pinfunction "4_4") (pintype "bidirectional"))
      (node (ref "U2") (pin "38") (pinfunction "START_38") (pintype "input"))
    )
    (net (code "6") (name "ADS_~{CS}") (class "Default")
      (node (ref "TEENSY") (pin "10") (pinfunction "10_10") (pintype "bidirectional"))
      (node (ref "U2") (pin "39") (pinfunction "~{CS}_39") (pintype "input"))
    )
    (net (code "7") (name "ADS_~{DRDY}") (class "Default")
      (node (ref "TEENSY") (pin "5") (pinfunction "5_5") (pintype "bidirectional"))
      (node (ref "U2") (pin "47") (pinfunction "~{DRDY}_47") (pintype "output"))
    )
    (net (code "8") (name "ADS_~{PWDN}") (class "Default")
      (node (ref "R39") (pin "2") (pinfunction "2_2") (pintype "passive"))
      (node (ref "TEENSY") (pin "2") (pinfunction "2_2") (pintype "bidirectional"))
      (node (ref "U2") (pin "35") (pinfunction "~{PWDN}_35") (pintype "input"))
    )
    (net (code "9") (name "ADS_~{RESET}") (class "Default")
      (node (ref "R40") (pin "2") (pinfunction "2_2") (pintype "passive"))
      (node (ref "TEENSY") (pin "3") (pinfunction "3_3") (pintype "bidirectional"))
      (node (ref "U2") (pin "36") (pinfunction "~{RESET}_36") (pintype "input"))
    )
    (net (code "10") (name "AINN1") (class "Default")
      (node (ref "D9") (pin "2") (pinfunction "2_2") (pintype "passive"))
      (node (ref "R17") (pin "1") (pinfunction "1_1") (pintype "passive"))
      (node (ref "SV2") (pin "4") (pinfunction "4_4") (pintype "passive"))
    )
    (net (code "11") (name "AINN2") (class "Default")
      (node (ref "D10") (pin "2") (pinfunction "2_2") (pintype "passive"))
      (node (ref "R19") (pin "1") (pinfunction "1_1") (pintype "passive"))
      (node (ref "SV2") (pin "8") (pinfunction "8_8") (pintype "passive"))
    )
    (net (code "12") (name "AINN3") (class "Default")
      (node (ref "D11") (pin "2") (pinfunction "2_2") (pintype "passive"))
      (node (ref "R21") (pin "1") (pinfunction "1_1") (pintype "passive"))
      (node (ref "SV2") (pin "12") (pinfunction "12_12") (pintype "passive"))
    )
    (net (code "13") (name "AINN4") (class "Default")
      (node (ref "D12") (pin "2") (pinfunction "2_2") (pintype "passive"))
      (node (ref "R23") (pin "1") (pinfunction "1_1") (pintype "passive"))
      (node (ref "SV2") (pin "16") (pinfunction "16_16") (pintype "passive"))
    )
    (net (code "14") (name "AINN5") (class "Default")
      (node (ref "D13") (pin "2") (pinfunction "2_2") (pintype "passive"))
      (node (ref "R25") (pin "1") (pinfunction "1_1") (pintype "passive"))
      (node (ref "SV2") (pin "20") (pinfunction "20_20") (pintype "passive"))
    )
    (net (code "15") (name "AINN6") (class "Default")
      (node (ref "D14") (pin "2") (pinfunction "2_2") (pintype "passive"))
      (node (ref "R27") (pin "1") (pinfunction "1_1") (pintype "passive"))
      (node (ref "SV2") (pin "24") (pinfunction "24_24") (pintype "passive"))
    )
    (net (code "16") (name "AINN7") (class "Default")
      (node (ref "D15") (pin "2") (pinfunction "2_2") (pintype "passive"))
      (node (ref "R29") (pin "1") (pinfunction "1_1") (pintype "passive"))
      (node (ref "SV2") (pin "28") (pinfunction "28_28") (pintype "passive"))
    )
    (net (code "17") (name "AINN8") (class "Default")
      (node (ref "D16") (pin "2") (pinfunction "2_2") (pintype "passive"))
      (node (ref "R31") (pin "1") (pinfunction "1_1") (pintype "passive"))
      (node (ref "SV2") (pin "32") (pinfunction "32_32") (pintype "passive"))
    )
    (net (code "18") (name "AINP1") (class "Default")
      (node (ref "D1") (pin "2") (pinfunction "2_2") (pintype "passive"))
      (node (ref "R1") (pin "1") (pinfunction "1_1") (pintype "passive"))
      (node (ref "SV2") (pin "3") (pinfunction "3_3") (pintype "passive"))
    )
    (net (code "19") (name "AINP2") (class "Default")
      (node (ref "D2") (pin "2") (pinfunction "2_2") (pintype "passive"))
      (node (ref "R3") (pin "1") (pinfunction "1_1") (pintype "passive"))
      (node (ref "SV2") (pin "7") (pinfunction "7_7") (pintype "passive"))
    )
    (net (code "20") (name "AINP3") (class "Default")
      (node (ref "D3") (pin "2") (pinfunction "2_2") (pintype "passive"))
      (node (ref "R5") (pin "1") (pinfunction "1_1") (pintype "passive"))
      (node (ref "SV2") (pin "11") (pinfunction "11_11") (pintype "passive"))
    )
    (net (code "21") (name "AINP4") (class "Default")
      (node (ref "D4") (pin "2") (pinfunction "2_2") (pintype "passive"))
      (node (ref "R7") (pin "1") (pinfunction "1_1") (pintype "passive"))
      (node (ref "SV2") (pin "15") (pinfunction "15_15") (pintype "passive"))
    )
    (net (code "22") (name "AINP5") (class "Default")
      (node (ref "D5") (pin "2") (pinfunction "2_2") (pintype "passive"))
      (node (ref "R9") (pin "1") (pinfunction "1_1") (pintype "passive"))
      (node (ref "SV2") (pin "19") (pinfunction "19_19") (pintype "passive"))
    )
    (net (code "23") (name "AINP6") (class "Default")
      (node (ref "D6") (pin "2") (pinfunction "2_2") (pintype "passive"))
      (node (ref "R11") (pin "1") (pinfunction "1_1") (pintype "passive"))
      (node (ref "SV2") (pin "23") (pinfunction "23_23") (pintype "passive"))
    )
    (net (code "24") (name "AINP7") (class "Default")
      (node (ref "D7") (pin "2") (pinfunction "2_2") (pintype "passive"))
      (node (ref "R13") (pin "1") (pinfunction "1_1") (pintype "passive"))
      (node (ref "SV2") (pin "27") (pinfunction "27_27") (pintype "passive"))
    )
    (net (code "25") (name "AINP8") (class "Default")
      (node (ref "D8") (pin "2") (pinfunction "2_2") (pintype "passive"))
      (node (ref "R15") (pin "1") (pinfunction "1_1") (pintype "passive"))
      (node (ref "SV2") (pin "31") (pinfunction "31_31") (pintype "passive"))
    )
    (net (code "26") (name "BIASOUT") (class "Default")
      (node (ref "C35") (pin "2") (pinfunction "2_2") (pintype "passive"))
      (node (ref "R35") (pin "2") (pinfunction "2_2") (pintype "passive"))
      (node (ref "SV1") (pin "5") (pinfunction "5_5") (pintype "passive"))
      (node (ref "SV1") (pin "7") (pinfunction "7_7") (pintype "passive"))
      (node (ref "SV1") (pin "9") (pinfunction "9_9") (pintype "passive"))
      (node (ref "U2") (pin "63") (pinfunction "RLDOUT_63") (pintype "output"))
    )
    (net (code "27") (name "GND") (class "Default")
      (node (ref "C1") (pin "1") (pinfunction "1_1") (pintype "passive"))
      (node (ref "C10") (pin "1") (pinfunction "1_1") (pintype "passive"))
      (node (ref "C11") (pin "1") (pinfunction "1_1") (pintype "passive"))
      (node (ref "C12") (pin "1") (pinfunction "1_1") (pintype "passive"))
      (node (ref "C13") (pin "1") (pinfunction "1_1") (pintype "passive"))
      (node (ref "C14") (pin "1") (pinfunction "1_1") (pintype "passive"))
      (node (ref "C15") (pin "1") (pinfunction "1_1") (pintype "passive"))
      (node (ref "C16") (pin "1") (pinfunction "1_1") (pintype "passive"))
      (node (ref "C17") (pin "1") (pinfunction "1_1") (pintype "passive"))
      (node (ref "C18") (pin "1") (pinfunction "1_1") (pintype "passive"))
      (node (ref "C19") (pin "1") (pinfunction "1_1") (pintype "passive"))
      (node (ref "C2") (pin "1") (pinfunction "1_1") (pintype "passive"))
      (node (ref "C20") (pin "1") (pinfunction "1_1") (pintype "passive"))
      (node (ref "C21") (pin "1") (pinfunction "1_1") (pintype "passive"))
      (node (ref "C22") (pin "1") (pinfunction "1_1") (pintype "passive"))
      (node (ref "C23") (pin "1") (pinfunction "1_1") (pintype "passive"))
      (node (ref "C24") (pin "1") (pinfunction "1_1") (pintype "passive"))
      (node (ref "C25") (pin "1") (pinfunction "1_1") (pintype "passive"))
      (node (ref "C26") (pin "1") (pinfunction "1_1") (pintype "passive"))
      (node (ref "C27") (pin "1") (pinfunction "1_1") (pintype "passive"))
      (node (ref "C28") (pin "1") (pinfunction "1_1") (pintype "passive"))
      (node (ref "C29") (pin "1") (pinfunction "1_1") (pintype "passive"))
      (node (ref "C3") (pin "1") (pinfunction "1_1") (pintype "passive"))
      (node (ref "C30") (pin "1") (pinfunction "1_1") (pintype "passive"))
      (node (ref "C31") (pin "1") (pinfunction "1_1") (pintype "passive"))
      (node (ref "C32") (pin "1") (pinfunction "1_1") (pintype "passive"))
      (node (ref "C34") (pin "1") (pinfunction "1_1") (pintype "passive"))
      (node (ref "C35") (pin "1") (pinfunction "1_1") (pintype "passive"))
      (node (ref "C36") (pin "2") (pinfunction "2_2") (pintype "passive"))
      (node (ref "C38") (pin "2") (pinfunction "2_2") (pintype "passive"))
      (node (ref "C39") (pin "2") (pinfunction "2_2") (pintype "passive"))
      (node (ref "C4") (pin "1") (pinfunction "1_1") (pintype "passive"))
      (node (ref "C40") (pin "2") (pinfunction "2_2") (pintype "passive"))
      (node (ref "C41") (pin "2") (pinfunction "2_2") (pintype "passive"))
      (node (ref "C42") (pin "2") (pinfunction "2_2") (pintype "passive"))
      (node (ref "C43") (pin "2") (pinfunction "2_2") (pintype "passive"))
      (node (ref "C44") (pin "2") (pinfunction "2_2") (pintype "passive"))
      (node (ref "C46") (pin "2") (pinfunction "2_2") (pintype "passive"))
      (node (ref "C47") (pin "2") (pinfunction "2_2") (pintype "passive"))
      (node (ref "C48") (pin "2") (pinfunction "2_2") (pintype "passive"))
      (node (ref "C5") (pin "1") (pinfunction "1_1") (pintype "passive"))
      (node (ref "C6") (pin "1") (pinfunction "1_1") (pintype "passive"))
      (node (ref "C65") (pin "2") (pinfunction "2_2") (pintype "passive"))
      (node (ref "C66") (pin "2") (pinfunction "2_2") (pintype "passive"))
      (node (ref "C67") (pin "2") (pinfunction "2_2") (pintype "passive"))
      (node (ref "C68") (pin "2") (pinfunction "2_2") (pintype "passive"))
      (node (ref "C69") (pin "2") (pinfunction "2_2") (pintype "passive"))
      (node (ref "C7") (pin "1") (pinfunction "1_1") (pintype "passive"))
      (node (ref "C70") (pin "2") (pinfunction "2_2") (pintype "passive"))
      (node (ref "C8") (pin "1") (pinfunction "1_1") (pintype "passive"))
      (node (ref "C9") (pin "1") (pinfunction "1_1") (pintype "passive"))
      (node (ref "CN1") (pin "GND") (pinfunction "GND_GND") (pintype "power_in"))
      (node (ref "D1") (pin "1") (pinfunction "1_1") (pintype "passive"))
      (node (ref "D10") (pin "1") (pinfunction "1_1") (pintype "passive"))
      (node (ref "D11") (pin "1") (pinfunction "1_1") (pintype "passive"))
      (node (ref "D12") (pin "1") (pinfunction "1_1") (pintype "passive"))
      (node (ref "D13") (pin "1") (pinfunction "1_1") (pintype "passive"))
      (node (ref "D14") (pin "1") (pinfunction "1_1") (pintype "passive"))
      (node (ref "D15") (pin "1") (pinfunction "1_1") (pintype "passive"))
      (node (ref "D16") (pin "1") (pinfunction "1_1") (pintype "passive"))
      (node (ref "D17") (pin "1") (pinfunction "1_1") (pintype "passive"))
      (node (ref "D2") (pin "1") (pinfunction "1_1") (pintype "passive"))
      (node (ref "D3") (pin "1") (pinfunction "1_1") (pintype "passive"))
      (node (ref "D4") (pin "1") (pinfunction "1_1") (pintype "passive"))
      (node (ref "D5") (pin "1") (pinfunction "1_1") (pintype "passive"))
      (node (ref "D6") (pin "1") (pinfunction "1_1") (pintype "passive"))
      (node (ref "D7") (pin "1") (pinfunction "1_1") (pintype "passive"))
      (node (ref "D8") (pin "1") (pinfunction "1_1") (pintype "passive"))
      (node (ref "D9") (pin "1") (pinfunction "1_1") (pintype "passive"))
      (node (ref "JP1") (pin "2") (pinfunction "2_2") (pintype "passive"))
      (node (ref "Q2") (pin "1") (pinfunction "S_1") (pintype "passive"))
      (node (ref "Q2") (pin "2") (pinfunction "S_2") (pintype "passive"))
      (node (ref "Q2") (pin "3") (pinfunction "S_3") (pintype "passive"))
      (node (ref "R36") (pin "1") (pinfunction "1_1") (pintype "passive"))
      (node (ref "R39") (pin "1") (pinfunction "1_1") (pintype "passive"))
      (node (ref "R40") (pin "1") (pinfunction "1_1") (pintype "passive"))
      (node (ref "R41") (pin "1") (pinfunction "1_1") (pintype "passive"))
      (node (ref "R43") (pin "2") (pinfunction "2_2") (pintype "passive"))
      (node (ref "R44") (pin "2") (pinfunction "2_2") (pintype "passive"))
      (node (ref "R46") (pin "1") (pinfunction "1_1") (pintype "passive"))
      (node (ref "R47") (pin "1") (pinfunction "1_1") (pintype "passive"))
      (node (ref "R49") (pin "1") (pinfunction "1_1") (pintype "passive"))
      (node (ref "R50") (pin "1") (pinfunction "1_1") (pintype "passive"))
      (node (ref "R51") (pin "1") (pinfunction "1_1") (pintype "passive"))
      (node (ref "S1") (pin "1") (pinfunction "P_1") (pintype "passive"))
      (node (ref "SV2") (pin "1") (pinfunction "1_1") (pintype "passive"))
      (node (ref "SV2") (pin "10") (pinfunction "10_10") (pintype "passive"))
      (node (ref "SV2") (pin "13") (pinfunction "13_13") (pintype "passive"))
      (node (ref "SV2") (pin "14") (pinfunction "14_14") (pintype "passive"))
      (node (ref "SV2") (pin "17") (pinfunction "17_17") (pintype "passive"))
      (node (ref "SV2") (pin "18") (pinfunction "18_18") (pintype "passive"))
      (node (ref "SV2") (pin "2") (pinfunction "2_2") (pintype "passive"))
      (node (ref "SV2") (pin "21") (pinfunction "21_21") (pintype "passive"))
      (node (ref "SV2") (pin "22") (pinfunction "22_22") (pintype "passive"))
      (node (ref "SV2") (pin "25") (pinfunction "25_25") (pintype "passive"))
      (node (ref "SV2") (pin "26") (pinfunction "26_26") (pintype "passive"))
      (node (ref "SV2") (pin "29") (pinfunction "29_29") (pintype "passive"))
      (node (ref "SV2") (pin "30") (pinfunction "30_30") (pintype "passive"))
      (node (ref "SV2") (pin "33") (pinfunction "33_33") (pintype "passive"))
      (node (ref "SV2") (pin "34") (pinfunction "34_34") (pintype "passive"))
      (node (ref "SV2") (pin "35") (pinfunction "35_35") (pintype "passive"))
      (node (ref "SV2") (pin "36") (pinfunction "36_36") (pintype "passive"))
      (node (ref "SV2") (pin "37") (pinfunction "37_37") (pintype "passive"))
      (node (ref "SV2") (pin "39") (pinfunction "39_39") (pintype "passive"))
      (node (ref "SV2") (pin "40") (pinfunction "40_40") (pintype "passive"))
      (node (ref "SV2") (pin "5") (pinfunction "5_5") (pintype "passive"))
      (node (ref "SV2") (pin "6") (pinfunction "6_6") (pintype "passive"))
      (node (ref "SV2") (pin "9") (pinfunction "9_9") (pintype "passive"))
      (node (ref "TEENSY") (pin "AGND") (pinfunction "AGND_AGND") (pintype "power_in"))
      (node (ref "TEENSY") (pin "GND") (pinfunction "GND_GND") (pintype "power_in"))
      (node (ref "TEENSY") (pin "GND1") (pinfunction "GND_GND1") (pintype "power_in"))
      (node (ref "U1") (pin "2") (pinfunction "GND_2") (pintype "power_in"))
      (node (ref "U2") (pin "31") (pinfunction "RESV1_31") (pintype "input"))
      (node (ref "U2") (pin "33") (pinfunction "DGND_33") (pintype "power_in"))
      (node (ref "U2") (pin "49") (pinfunction "DGND_49") (pintype "power_in"))
      (node (ref "U2") (pin "51") (pinfunction "DGND_51") (pintype "power_in"))
      (node (ref "U3") (pin "1") (pinfunction "GND_1") (pintype "passive"))
      (node (ref "U4") (pin "1") (pinfunction "GND_1") (pintype "power_in"))
      (node (ref "U5") (pin "2") (pinfunction "GND_2") (pintype "power_in"))
      (node (ref "U6") (pin "2") (pinfunction "VSS_2") (pintype "power_in"))
      (node (ref "U6") (pin "5") (pinfunction "~{CE}_5") (pintype "input"))
      (node (ref "U6") (pin "6") (pinfunction "VBAT_6") (pintype "input"))
      (node (ref "U6") (pin "9") (pinfunction "EPAD_9") (pintype "power_in"))
      (node (ref "U8") (pin "2") (pinfunction "VSS_2") (pintype "power_in"))
      (node (ref "X1") (pin "2") (pinfunction "GND_2") (pintype "power_in"))
    )
    (net (code "28") (name "INN1") (class "Default")
      (node (ref "C18") (pin "2") (pinfunction "2_2") (pintype "passive"))
      (node (ref "R18") (pin "2") (pinfunction "2_2") (pintype "passive"))
      (node (ref "U2") (pin "15") (pinfunction "IN1N_15") (pintype "input"))
    )
    (net (code "29") (name "INN2") (class "Default")
      (node (ref "C20") (pin "2") (pinfunction "2_2") (pintype "passive"))
      (node (ref "R20") (pin "2") (pinfunction "2_2") (pintype "passive"))
      (node (ref "U2") (pin "13") (pinfunction "IN2N_13") (pintype "input"))
    )
    (net (code "30") (name "INN3") (class "Default")
      (node (ref "C22") (pin "2") (pinfunction "2_2") (pintype "passive"))
      (node (ref "R22") (pin "2") (pinfunction "2_2") (pintype "passive"))
      (node (ref "U2") (pin "11") (pinfunction "IN3N_11") (pintype "input"))
    )
    (net (code "31") (name "INN4") (class "Default")
      (node (ref "C24") (pin "2") (pinfunction "2_2") (pintype "passive"))
      (node (ref "R24") (pin "2") (pinfunction "2_2") (pintype "passive"))
      (node (ref "U2") (pin "9") (pinfunction "IN4N_9") (pintype "input"))
    )
    (net (code "32") (name "INN5") (class "Default")
      (node (ref "C26") (pin "2") (pinfunction "2_2") (pintype "passive"))
      (node (ref "R26") (pin "2") (pinfunction "2_2") (pintype "passive"))
      (node (ref "U2") (pin "7") (pinfunction "IN5N_7") (pintype "input"))
    )
    (net (code "33") (name "INN6") (class "Default")
      (node (ref "C28") (pin "2") (pinfunction "2_2") (pintype "passive"))
      (node (ref "R28") (pin "2") (pinfunction "2_2") (pintype "passive"))
      (node (ref "U2") (pin "5") (pinfunction "IN6N_5") (pintype "input"))
    )
    (net (code "34") (name "INN7") (class "Default")
      (node (ref "C30") (pin "2") (pinfunction "2_2") (pintype "passive"))
      (node (ref "R30") (pin "2") (pinfunction "2_2") (pintype "passive"))
      (node (ref "U2") (pin "3") (pinfunction "IN7N_3") (pintype "input"))
    )
    (net (code "35") (name "INN8") (class "Default")
      (node (ref "C32") (pin "2") (pinfunction "2_2") (pintype "passive"))
      (node (ref "R32") (pin "2") (pinfunction "2_2") (pintype "passive"))
      (node (ref "U2") (pin "1") (pinfunction "IN8N_1") (pintype "input"))
    )
    (net (code "36") (name "INP1") (class "Default")
      (node (ref "C2") (pin "2") (pinfunction "2_2") (pintype "passive"))
      (node (ref "R2") (pin "2") (pinfunction "2_2") (pintype "passive"))
      (node (ref "U2") (pin "16") (pinfunction "IN1P_16") (pintype "input"))
    )
    (net (code "37") (name "INP2") (class "Default")
      (node (ref "C4") (pin "2") (pinfunction "2_2") (pintype "passive"))
      (node (ref "R4") (pin "2") (pinfunction "2_2") (pintype "passive"))
      (node (ref "U2") (pin "14") (pinfunction "IN2P_14") (pintype "input"))
    )
    (net (code "38") (name "INP3") (class "Default")
      (node (ref "C6") (pin "2") (pinfunction "2_2") (pintype "passive"))
      (node (ref "R6") (pin "2") (pinfunction "2_2") (pintype "passive"))
      (node (ref "U2") (pin "12") (pinfunction "IN3P_12") (pintype "input"))
    )
    (net (code "39") (name "INP4") (class "Default")
      (node (ref "C8") (pin "2") (pinfunction "2_2") (pintype "passive"))
      (node (ref "R8") (pin "2") (pinfunction "2_2") (pintype "passive"))
      (node (ref "U2") (pin "10") (pinfunction "IN4P_10") (pintype "input"))
    )
    (net (code "40") (name "INP5") (class "Default")
      (node (ref "C10") (pin "2") (pinfunction "2_2") (pintype "passive"))
      (node (ref "R10") (pin "2") (pinfunction "2_2") (pintype "passive"))
      (node (ref "U2") (pin "8") (pinfunction "IN5P_8") (pintype "input"))
    )
    (net (code "41") (name "INP6") (class "Default")
      (node (ref "C12") (pin "2") (pinfunction "2_2") (pintype "passive"))
      (node (ref "R12") (pin "2") (pinfunction "2_2") (pintype "passive"))
      (node (ref "U2") (pin "6") (pinfunction "IN6P_6") (pintype "input"))
    )
    (net (code "42") (name "INP7") (class "Default")
      (node (ref "C14") (pin "2") (pinfunction "2_2") (pintype "passive"))
      (node (ref "R14") (pin "2") (pinfunction "2_2") (pintype "passive"))
      (node (ref "U2") (pin "4") (pinfunction "IN7P_4") (pintype "input"))
    )
    (net (code "43") (name "INP8") (class "Default")
      (node (ref "C16") (pin "2") (pinfunction "2_2") (pintype "passive"))
      (node (ref "R16") (pin "2") (pinfunction "2_2") (pintype "passive"))
      (node (ref "U2") (pin "2") (pinfunction "IN8P_2") (pintype "input"))
    )
    (net (code "44") (name "MISO") (class "Default")
      (node (ref "TEENSY") (pin "12") (pinfunction "12_12") (pintype "bidirectional"))
      (node (ref "U1") (pin "9") (pinfunction "MISO_9") (pintype "output"))
      (node (ref "U2") (pin "43") (pinfunction "DOUT_43") (pintype "output"))
    )
    (net (code "45") (name "MOSI") (class "Default")
      (node (ref "TEENSY") (pin "11") (pinfunction "11_11") (pintype "bidirectional"))
      (node (ref "U1") (pin "8") (pinfunction "MOSI_8") (pintype "input"))
      (node (ref "U2") (pin "34") (pinfunction "DIN_34") (pintype "input"))
    )
    (net (code "46") (name "NRF_RDYN") (class "Default")
      (node (ref "TEENSY") (pin "8") (pinfunction "8_8") (pintype "bidirectional"))
      (node (ref "U1") (pin "10") (pinfunction "RDYN_10") (pintype "bidirectional"))
    )
    (net (code "47") (name "NRF_REQN") (class "Default")
      (node (ref "TEENSY") (pin "9") (pinfunction "9_9") (pintype "bidirectional"))
      (node (ref "U1") (pin "7") (pinfunction "REQN_7") (pintype "bidirectional"))
    )
    (net (code "48") (name "NRF_~{RESET}") (class "Default")
      (node (ref "R41") (pin "2") (pinfunction "2_2") (pintype "passive"))
      (node (ref "TEENSY") (pin "7") (pinfunction "7_7") (pintype "bidirectional"))
      (node (ref "U1") (pin "3") (pinfunction "~{RST}_3") (pintype "input"))
    )
    (net (code "49") (name "Net-(BATCON-1)") (class "Default")
      (node (ref "BATCON") (pin "2") (pinfunction "1_2") (pintype "passive"))
      (node (ref "C45") (pin "2") (pinfunction "2_2") (pintype "passive"))
      (node (ref "Q1") (pin "1") (pinfunction "S_1") (pintype "passive"))
      (node (ref "Q1") (pin "2") (pinfunction "S_2") (pintype "passive"))
      (node (ref "Q1") (pin "3") (pinfunction "S_3") (pintype "passive"))
      (node (ref "U7") (pin "4") (pinfunction "VSS_4") (pintype "power_in"))
    )
    (net (code "50") (name "Net-(C1-Pad2)") (class "Default")
      (node (ref "C1") (pin "2") (pinfunction "2_2") (pintype "passive"))
      (node (ref "R1") (pin "2") (pinfunction "2_2") (pintype "passive"))
      (node (ref "R2") (pin "1") (pinfunction "1_1") (pintype "passive"))
    )
    (net (code "51") (name "Net-(C3-Pad2)") (class "Default")
      (node (ref "C3") (pin "2") (pinfunction "2_2") (pintype "passive"))
      (node (ref "R3") (pin "2") (pinfunction "2_2") (pintype "passive"))
      (node (ref "R4") (pin "1") (pinfunction "1_1") (pintype "passive"))
    )
    (net (code "52") (name "Net-(C5-Pad2)") (class "Default")
      (node (ref "C5") (pin "2") (pinfunction "2_2") (pintype "passive"))
      (node (ref "R5") (pin "2") (pinfunction "2_2") (pintype "passive"))
      (node (ref "R6") (pin "1") (pinfunction "1_1") (pintype "passive"))
    )
    (net (code "53") (name "Net-(C7-Pad2)") (class "Default")
      (node (ref "C7") (pin "2") (pinfunction "2_2") (pintype "passive"))
      (node (ref "R7") (pin "2") (pinfunction "2_2") (pintype "passive"))
      (node (ref "R8") (pin "1") (pinfunction "1_1") (pintype "passive"))
    )
    (net (code "54") (name "Net-(C9-Pad2)") (class "Default")
      (node (ref "C9") (pin "2") (pinfunction "2_2") (pintype "passive"))
      (node (ref "R10") (pin "1") (pinfunction "1_1") (pintype "passive"))
      (node (ref "R9") (pin "2") (pinfunction "2_2") (pintype "passive"))
    )
    (net (code "55") (name "Net-(C11-Pad2)") (class "Default")
      (node (ref "C11") (pin "2") (pinfunction "2_2") (pintype "passive"))
      (node (ref "R11") (pin "2") (pinfunction "2_2") (pintype "passive"))
      (node (ref "R12") (pin "1") (pinfunction "1_1") (pintype "passive"))
    )
    (net (code "56") (name "Net-(C13-Pad2)") (class "Default")
      (node (ref "C13") (pin "2") (pinfunction "2_2") (pintype "passive"))
      (node (ref "R13") (pin "2") (pinfunction "2_2") (pintype "passive"))
      (node (ref "R14") (pin "1") (pinfunction "1_1") (pintype "passive"))
    )
    (net (code "57") (name "Net-(C15-Pad2)") (class "Default")
      (node (ref "C15") (pin "2") (pinfunction "2_2") (pintype "passive"))
      (node (ref "R15") (pin "2") (pinfunction "2_2") (pintype "passive"))
      (node (ref "R16") (pin "1") (pinfunction "1_1") (pintype "passive"))
    )
    (net (code "58") (name "Net-(C17-Pad2)") (class "Default")
      (node (ref "C17") (pin "2") (pinfunction "2_2") (pintype "passive"))
      (node (ref "R17") (pin "2") (pinfunction "2_2") (pintype "passive"))
      (node (ref "R18") (pin "1") (pinfunction "1_1") (pintype "passive"))
    )
    (net (code "59") (name "Net-(C19-Pad2)") (class "Default")
      (node (ref "C19") (pin "2") (pinfunction "2_2") (pintype "passive"))
      (node (ref "R19") (pin "2") (pinfunction "2_2") (pintype "passive"))
      (node (ref "R20") (pin "1") (pinfunction "1_1") (pintype "passive"))
    )
    (net (code "60") (name "Net-(C21-Pad2)") (class "Default")
      (node (ref "C21") (pin "2") (pinfunction "2_2") (pintype "passive"))
      (node (ref "R21") (pin "2") (pinfunction "2_2") (pintype "passive"))
      (node (ref "R22") (pin "1") (pinfunction "1_1") (pintype "passive"))
    )
    (net (code "61") (name "Net-(C23-Pad2)") (class "Default")
      (node (ref "C23") (pin "2") (pinfunction "2_2") (pintype "passive"))
      (node (ref "R23") (pin "2") (pinfunction "2_2") (pintype "passive"))
      (node (ref "R24") (pin "1") (pinfunction "1_1") (pintype "passive"))
    )
    (net (code "62") (name "Net-(C25-Pad2)") (class "Default")
      (node (ref "C25") (pin "2") (pinfunction "2_2") (pintype "passive"))
      (node (ref "R25") (pin "2") (pinfunction "2_2") (pintype "passive"))
      (node (ref "R26") (pin "1") (pinfunction "1_1") (pintype "passive"))
    )
    (net (code "63") (name "Net-(C27-Pad2)") (class "Default")
      (node (ref "C27") (pin "2") (pinfunction "2_2") (pintype "passive"))
      (node (ref "R27") (pin "2") (pinfunction "2_2") (pintype "passive"))
      (node (ref "R28") (pin "1") (pinfunction "1_1") (pintype "passive"))
    )
    (net (code "64") (name "Net-(C29-Pad2)") (class "Default")
      (node (ref "C29") (pin "2") (pinfunction "2_2") (pintype "passive"))
      (node (ref "R29") (pin "2") (pinfunction "2_2") (pintype "passive"))
      (node (ref "R30") (pin "1") (pinfunction "1_1") (pintype "passive"))
    )
    (net (code "65") (name "Net-(C31-Pad2)") (class "Default")
      (node (ref "C31") (pin "2") (pinfunction "2_2") (pintype "passive"))
      (node (ref "R31") (pin "2") (pinfunction "2_2") (pintype "passive"))
      (node (ref "R32") (pin "1") (pinfunction "1_1") (pintype "passive"))
    )
    (net (code "66") (name "Net-(C33-Pad2)") (class "Default")
      (node (ref "C33") (pin "2") (pinfunction "2_2") (pintype "passive"))
      (node (ref "R33") (pin "1") (pinfunction "1_1") (pintype "passive"))
      (node (ref "SV1") (pin "8") (pinfunction "8_8") (pintype "passive"))
    )
    (net (code "67") (name "Net-(C34-Pad2)") (class "Default")
      (node (ref "C34") (pin "2") (pinfunction "2_2") (pintype "passive"))
      (node (ref "R34") (pin "2") (pinfunction "2_2") (pintype "passive"))
      (node (ref "R35") (pin "1") (pinfunction "1_1") (pintype "passive"))
    )
    (net (code "68") (name "Net-(LED1-PadA)") (class "Default")
      (node (ref "LED1") (pin "A") (pinfunction "A_A") (pintype "passive"))
      (node (ref "TEENSY") (pin "16/A2") (pinfunction "16/A2_16/A2") (pintype "bidirectional"))
    )
    (net (code "69") (name "Net-(LED1-PadC)") (class "Default")
      (node (ref "LED1") (pin "C") (pinfunction "C_C") (pintype "passive"))
      (node (ref "R49") (pin "2") (pinfunction "2_2") (pintype "passive"))
    )
    (net (code "70") (name "Net-(LED2-PadA)") (class "Default")
      (node (ref "LED2") (pin "A") (pinfunction "A_A") (pintype "passive"))
      (node (ref "TEENSY") (pin "17/A3") (pinfunction "17/A3_17/A3") (pintype "bidirectional"))
    )
    (net (code "71") (name "Net-(LED2-PadC)") (class "Default")
      (node (ref "LED2") (pin "C") (pinfunction "C_C") (pintype "passive"))
      (node (ref "R50") (pin "2") (pinfunction "2_2") (pintype "passive"))
    )
    (net (code "72") (name "Net-(LED3-PadA)") (class "Default")
      (node (ref "LED3") (pin "A") (pinfunction "A_A") (pintype "passive"))
      (node (ref "TEENSY") (pin "18/A4") (pinfunction "18/A4_18/A4") (pintype "bidirectional"))
    )
    (net (code "73") (name "Net-(LED3-PadC)") (class "Default")
      (node (ref "LED3") (pin "C") (pinfunction "C_C") (pintype "passive"))
      (node (ref "R51") (pin "2") (pinfunction "2_2") (pintype "passive"))
    )
    (net (code "74") (name "Net-(Q1-D-Pad5)") (class "Default")
      (node (ref "Q1") (pin "5") (pinfunction "D_5") (pintype "passive"))
      (node (ref "Q1") (pin "6") (pinfunction "D_6") (pintype "passive"))
      (node (ref "Q1") (pin "7") (pinfunction "D_7") (pintype "passive"))
      (node (ref "Q1") (pin "8") (pinfunction "D_8") (pintype "passive"))
      (node (ref "Q2") (pin "5") (pinfunction "D_5") (pintype "passive"))
      (node (ref "Q2") (pin "6") (pinfunction "D_6") (pintype "passive"))
      (node (ref "Q2") (pin "7") (pinfunction "D_7") (pintype "passive"))
      (node (ref "Q2") (pin "8") (pinfunction "D_8") (pintype "passive"))
    )
    (net (code "75") (name "Net-(Q1-G)") (class "Default")
      (node (ref "Q1") (pin "4") (pinfunction "G_4") (pintype "passive"))
      (node (ref "U7") (pin "3") (pinfunction "DOUT_3") (pintype "passive"))
    )
    (net (code "76") (name "Net-(Q2-G)") (class "Default")
      (node (ref "Q2") (pin "4") (pinfunction "G_4") (pintype "passive"))
      (node (ref "U7") (pin "2") (pinfunction "COUT_2") (pintype "passive"))
    )
    (net (code "77") (name "Net-(S1-S)") (class "Default")
      (node (ref "R48") (pin "1") (pinfunction "1_1") (pintype "passive"))
      (node (ref "S1") (pin "2") (pinfunction "S_2") (pintype "passive"))
      (node (ref "TEENSY") (pin "15/A1") (pinfunction "15/A1_15/A1") (pintype "bidirectional"))
    )
    (net (code "78") (name "Net-(U2-CLK)") (class "Default")
      (node (ref "U2") (pin "37") (pinfunction "CLK_37") (pintype "bidirectional"))
      (node (ref "X1") (pin "3") (pinfunction "OUT_3") (pintype "output"))
    )
    (net (code "79") (name "Net-(U2-CLKSEL)") (class "Default")
      (node (ref "JP1") (pin "1") (pinfunction "1_1") (pintype "passive"))
      (node (ref "R38") (pin "1") (pinfunction "1_1") (pintype "passive"))
      (node (ref "U2") (pin "52") (pinfunction "CLKSEL_52") (pintype "input"))
    )
    (net (code "80") (name "Net-(U2-RLDIN)") (class "Default")
      (node (ref "SV1") (pin "10") (pinfunction "10_10") (pintype "passive"))
      (node (ref "SV1") (pin "6") (pinfunction "6_6") (pintype "passive"))
      (node (ref "U2") (pin "62") (pinfunction "RLDIN_62") (pintype "input"))
    )
    (net (code "81") (name "Net-(U2-RLDINV)") (class "Default")
      (node (ref "C33") (pin "1") (pinfunction "1_1") (pintype "passive"))
      (node (ref "R33") (pin "2") (pinfunction "2_2") (pintype "passive"))
      (node (ref "SV1") (pin "4") (pinfunction "4_4") (pintype "passive"))
      (node (ref "U2") (pin "61") (pinfunction "RLDINV_61") (pintype "bidirectional"))
    )
    (net (code "82") (name "Net-(U2-RLDREF)") (class "Default")
      (node (ref "SV1") (pin "2") (pinfunction "2_2") (pintype "passive"))
      (node (ref "U2") (pin "60") (pinfunction "RLDREF_60") (pintype "input"))
    )
    (net (code "83") (name "Net-(U2-VREFP)") (class "Default")
      (node (ref "C62") (pin "1") (pinfunction "1_1") (pintype "passive"))
      (node (ref "C63") (pin "1") (pinfunction "1_1") (pintype "passive"))
      (node (ref "U2") (pin "24") (pinfunction "VREFP_24") (pintype "bidirectional"))
    )
    (net (code "84") (name "Net-(U2-WCT)") (class "Default")
      (node (ref "C64") (pin "1") (pinfunction "1_1") (pintype "passive"))
      (node (ref "U2") (pin "64") (pinfunction "WCT_64") (pintype "output"))
    )
    (net (code "85") (name "Net-(U3-CAP+)") (class "Default")
      (node (ref "C37") (pin "1") (pinfunction "1_1") (pintype "passive"))
      (node (ref "U3") (pin "6") (pinfunction "CAP+_6") (pintype "passive"))
    )
    (net (code "86") (name "Net-(U3-CAP-)") (class "Default")
      (node (ref "C37") (pin "2") (pinfunction "2_2") (pintype "passive"))
      (node (ref "U3") (pin "3") (pinfunction "CAP-_3") (pintype "passive"))
    )
    (net (code "87") (name "Net-(U3-OUT)") (class "Default")
      (node (ref "C39") (pin "1") (pinfunction "1_1") (pintype "passive"))
      (node (ref "U3") (pin "2") (pinfunction "OUT_2") (pintype "output"))
      (node (ref "U4") (pin "2") (pinfunction "IN_2") (pintype "input"))
    )
    (net (code "88") (name "Net-(U4-FB{slash}NR)") (class "Default")
      (node (ref "C40") (pin "1") (pinfunction "1_1") (pintype "passive"))
      (node (ref "R44") (pin "1") (pinfunction "1_1") (pintype "passive"))
      (node (ref "R45") (pin "2") (pinfunction "2_2") (pintype "passive"))
      (node (ref "U4") (pin "4") (pinfunction "FB/NR_4") (pintype "passive"))
    )
    (net (code "89") (name "Net-(U5-NR{slash}FB)") (class "Default")
      (node (ref "C43") (pin "1") (pinfunction "1_1") (pintype "passive"))
      (node (ref "R42") (pin "2") (pinfunction "2_2") (pintype "passive"))
      (node (ref "R43") (pin "1") (pinfunction "1_1") (pintype "passive"))
      (node (ref "U5") (pin "4") (pinfunction "NR/FB_4") (pintype "passive"))
    )
    (net (code "90") (name "Net-(U6-IN)") (class "Default")
      (node (ref "C48") (pin "1") (pinfunction "1_1") (pintype "passive"))
      (node (ref "CN1") (pin "VBUS") (pinfunction "VBUS_VBUS") (pintype "power_in"))
      (node (ref "U6") (pin "1") (pinfunction "IN_1") (pintype "input"))
    )
    (net (code "91") (name "Net-(U6-OUT)") (class "Default")
      (node (ref "C46") (pin "1") (pinfunction "1_1") (pintype "passive"))
      (node (ref "C47") (pin "1") (pinfunction "1_1") (pintype "passive"))
      (node (ref "U6") (pin "8") (pinfunction "OUT_8") (pintype "output"))
      (node (ref "U8") (pin "1") (pinfunction "CE_1") (pintype "input"))
      (node (ref "U8") (pin "4") (pinfunction "VDD_4") (pintype "power_in"))
      (node (ref "U8") (pin "5") (pinfunction "PROG_5") (pintype "input"))
    )
    (net (code "92") (name "Net-(U7-BAT)") (class "Default")
      (node (ref "C45") (pin "1") (pinfunction "1_1") (pintype "passive"))
      (node (ref "R37") (pin "2") (pinfunction "2_2") (pintype "passive"))
      (node (ref "U7") (pin "5") (pinfunction "BAT_5") (pintype "passive"))
    )
    (net (code "93") (name "Net-(U7-V-)") (class "Default")
      (node (ref "R36") (pin "2") (pinfunction "2_2") (pintype "passive"))
      (node (ref "U7") (pin "6") (pinfunction "V-_6") (pintype "power_in"))
    )
    (net (code "94") (name "PSU_NEG") (class "Default")
      (node (ref "R47") (pin "2") (pinfunction "2_2") (pintype "passive"))
      (node (ref "TEENSY") (pin "1") (pinfunction "1_1") (pintype "bidirectional"))
      (node (ref "U3") (pin "4") (pinfunction "~{SD}_4") (pintype "input"))
      (node (ref "U4") (pin "3") (pinfunction "EN_3") (pintype "passive"))
    )
    (net (code "95") (name "PSU_POS") (class "Default")
      (node (ref "R46") (pin "2") (pinfunction "2_2") (pintype "passive"))
      (node (ref "TEENSY") (pin "0") (pinfunction "0_0") (pintype "bidirectional"))
      (node (ref "U5") (pin "3") (pinfunction "~{EN}_3") (pintype "passive"))
    )
    (net (code "96") (name "SCK") (class "Default")
      (node (ref "TEENSY") (pin "13") (pinfunction "13_13") (pintype "bidirectional"))
      (node (ref "U1") (pin "6") (pinfunction "SCK_6") (pintype "input"))
      (node (ref "U2") (pin "40") (pinfunction "SCLK_40") (pintype "input"))
    )
    (net (code "97") (name "SRB1") (class "Default")
      (node (ref "SV1") (pin "1") (pinfunction "1_1") (pintype "passive"))
      (node (ref "U2") (pin "17") (pinfunction "TESTP_PACE_OUT1_17") (pintype "bidirectional"))
    )
    (net (code "98") (name "SRB2") (class "Default")
      (node (ref "SV1") (pin "3") (pinfunction "3_3") (pintype "passive"))
      (node (ref "U2") (pin "18") (pinfunction "TESTN_PACE_OUT2_18") (pintype "bidirectional"))
    )
    (net (code "99") (name "V+") (class "Default")
      (node (ref "C49") (pin "1") (pinfunction "1_1") (pintype "passive"))
      (node (ref "C50") (pin "1") (pinfunction "1_1") (pintype "passive"))
      (node (ref "C51") (pin "1") (pinfunction "1_1") (pintype "passive"))
      (node (ref "C52") (pin "1") (pinfunction "1_1") (pintype "passive"))
      (node (ref "C53") (pin "1") (pinfunction "1_1") (pintype "passive"))
      (node (ref "C54") (pin "1") (pinfunction "1_1") (pintype "passive"))
      (node (ref "C55") (pin "1") (pinfunction "1_1") (pintype "passive"))
      (node (ref "C56") (pin "1") (pinfunction "1_1") (pintype "passive"))
      (node (ref "L1") (pin "1") (pinfunction "1_1") (pintype "passive"))
      (node (ref "U2") (pin "19") (pinfunction "AVDD_19") (pintype "power_in"))
      (node (ref "U2") (pin "21") (pinfunction "AVDD_21") (pintype "power_in"))
      (node (ref "U2") (pin "22") (pinfunction "AVDD_22") (pintype "power_in"))
      (node (ref "U2") (pin "54") (pinfunction "AVDD1_54") (pintype "power_in"))
      (node (ref "U2") (pin "56") (pinfunction "AVDD_56") (pintype "power_in"))
      (node (ref "U2") (pin "59") (pinfunction "AVDD_59") (pintype "power_in"))
    )
    (net (code "100") (name "V-") (class "Default")
      (node (ref "C49") (pin "2") (pinfunction "2_2") (pintype "passive"))
      (node (ref "C50") (pin "2") (pinfunction "2_2") (pintype "passive"))
      (node (ref "C51") (pin "2") (pinfunction "2_2") (pintype "passive"))
      (node (ref "C52") (pin "2") (pinfunction "2_2") (pintype "passive"))
      (node (ref "C53") (pin "2") (pinfunction "2_2") (pintype "passive"))
      (node (ref "C54") (pin "2") (pinfunction "2_2") (pintype "passive"))
      (node (ref "C55") (pin "2") (pinfunction "2_2") (pintype "passive"))
      (node (ref "C56") (pin "2") (pinfunction "2_2") (pintype "passive"))
      (node (ref "C57") (pin "2") (pinfunction "2_2") (pintype "passive"))
      (node (ref "C58") (pin "2") (pinfunction "2_2") (pintype "passive"))
      (node (ref "C59") (pin "2") (pinfunction "2_2") (pintype "passive"))
      (node (ref "C60") (pin "-") (pinfunction "-_-") (pintype "passive"))
      (node (ref "C61") (pin "2") (pinfunction "2_2") (pintype "passive"))
      (node (ref "C62") (pin "2") (pinfunction "2_2") (pintype "passive"))
      (node (ref "C63") (pin "2") (pinfunction "2_2") (pintype "passive"))
      (node (ref "C64") (pin "2") (pinfunction "2_2") (pintype "passive"))
      (node (ref "L2") (pin "2") (pinfunction "2_2") (pintype "passive"))
      (node (ref "U2") (pin "20") (pinfunction "AVSS_20") (pintype "power_in"))
      (node (ref "U2") (pin "23") (pinfunction "AVSS_23") (pintype "power_in"))
      (node (ref "U2") (pin "25") (pinfunction "VREFN_25") (pintype "input"))
      (node (ref "U2") (pin "32") (pinfunction "AVSS_32") (pintype "power_in"))
      (node (ref "U2") (pin "53") (pinfunction "AVSS1_53") (pintype "power_in"))
      (node (ref "U2") (pin "57") (pinfunction "AVSS_57") (pintype "power_in"))
      (node (ref "U2") (pin "58") (pinfunction "AVSS_58") (pintype "power_in"))
    )
    (net (code "101") (name "VBAT") (class "Default")
      (node (ref "BATCON") (pin "1") (pinfunction "2_1") (pintype "passive"))
      (node (ref "C38") (pin "1") (pinfunction "1_1") (pintype "passive"))
      (node (ref "C42") (pin "1") (pinfunction "1_1") (pintype "passive"))
      (node (ref "C67") (pin "1") (pinfunction "1_1") (pintype "passive"))
      (node (ref "R37") (pin "1") (pinfunction "1_1") (pintype "passive"))
      (node (ref "TEENSY") (pin "VIN") (pinfunction "VIN_VIN") (pintype "power_in"))
      (node (ref "U3") (pin "5") (pinfunction "V+_5") (pintype "power_in"))
      (node (ref "U5") (pin "1") (pinfunction "IN_1") (pintype "input"))
      (node (ref "U8") (pin "3") (pinfunction "VBAT_3") (pintype "bidirectional"))
    )
    (net (code "102") (name "VCAP1") (class "Default")
      (node (ref "C60") (pin "+") (pinfunction "+_+") (pintype "passive"))
      (node (ref "U2") (pin "28") (pinfunction "VCAP1_28") (pintype "passive"))
    )
    (net (code "103") (name "VCAP2") (class "Default")
      (node (ref "C59") (pin "1") (pinfunction "1_1") (pintype "passive"))
      (node (ref "U2") (pin "30") (pinfunction "VCAP2_30") (pintype "passive"))
    )
    (net (code "104") (name "VCAP3") (class "Default")
      (node (ref "C57") (pin "1") (pinfunction "1_1") (pintype "passive"))
      (node (ref "C58") (pin "1") (pinfunction "1_1") (pintype "passive"))
      (node (ref "U2") (pin "55") (pinfunction "VCAP3_55") (pintype "passive"))
    )
    (net (code "105") (name "VCAP4") (class "Default")
      (node (ref "C61") (pin "1") (pinfunction "1_1") (pintype "passive"))
      (node (ref "U2") (pin "26") (pinfunction "VCAP4_26") (pintype "output"))
    )
    (net (code "106") (name "unconnected-(CN1-PadD+)") (class "Default")
      (node (ref "CN1") (pin "D+") (pinfunction "D+_D+") (pintype "bidirectional"))
    )
    (net (code "107") (name "unconnected-(CN1-PadD-)") (class "Default")
      (node (ref "CN1") (pin "D-") (pinfunction "D-_D-") (pintype "bidirectional"))
    )
    (net (code "108") (name "unconnected-(CN1-PadID)") (class "Default")
      (node (ref "CN1") (pin "ID") (pinfunction "ID_ID") (pintype "bidirectional"))
    )
    (net (code "109") (name "unconnected-(TEENSY-Pad6)") (class "Default")
      (node (ref "TEENSY") (pin "6") (pinfunction "6_6") (pintype "bidirectional"))
    )
    (net (code "110") (name "unconnected-(TEENSY-Pad14{slash}A0)") (class "Default")
      (node (ref "TEENSY") (pin "14/A0") (pinfunction "14/A0_14/A0") (pintype "bidirectional"))
    )
    (net (code "111") (name "unconnected-(TEENSY-Pad19{slash}A5)") (class "Default")
      (node (ref "TEENSY") (pin "19/A5") (pinfunction "19/A5_19/A5") (pintype "bidirectional"))
    )
    (net (code "112") (name "unconnected-(TEENSY-Pad20{slash}A6)") (class "Default")
      (node (ref "TEENSY") (pin "20/A6") (pinfunction "20/A6_20/A6") (pintype "bidirectional"))
    )
    (net (code "113") (name "unconnected-(TEENSY-Pad21{slash}A7)") (class "Default")
      (node (ref "TEENSY") (pin "21/A7") (pinfunction "21/A7_21/A7") (pintype "bidirectional"))
    )
    (net (code "114") (name "unconnected-(TEENSY-Pad22{slash}A8)") (class "Default")
      (node (ref "TEENSY") (pin "22/A8") (pinfunction "22/A8_22/A8") (pintype "bidirectional"))
    )
    (net (code "115") (name "unconnected-(TEENSY-Pad23{slash}A9)") (class "Default")
      (node (ref "TEENSY") (pin "23/A9") (pinfunction "23/A9_23/A9") (pintype "bidirectional"))
    )
    (net (code "116") (name "unconnected-(TEENSY-PadPGM)") (class "Default")
      (node (ref "TEENSY") (pin "PGM") (pinfunction "PGM_PGM") (pintype "bidirectional"))
    )
    (net (code "117") (name "unconnected-(TEENSY-PadRESET)") (class "Default")
      (node (ref "TEENSY") (pin "RESET") (pinfunction "RESET_RESET") (pintype "bidirectional"))
    )
    (net (code "118") (name "unconnected-(TEENSY-PadVBAT)") (class "Default")
      (node (ref "TEENSY") (pin "VBAT") (pinfunction "VBAT_VBAT") (pintype "power_in"))
    )
    (net (code "119") (name "unconnected-(U1-RXD-Pad4)") (class "Default")
      (node (ref "U1") (pin "4") (pinfunction "RXD_4") (pintype "input"))
    )
    (net (code "120") (name "unconnected-(U1-TXD-Pad5)") (class "Default")
      (node (ref "U1") (pin "5") (pinfunction "TXD_5") (pintype "output"))
    )
    (net (code "121") (name "unconnected-(U2-DAISY_IN-Pad41)") (class "Default")
      (node (ref "U2") (pin "41") (pinfunction "DAISY_IN_41") (pintype "input"))
    )
    (net (code "122") (name "unconnected-(U2-GPIO1-Pad42)") (class "Default")
      (node (ref "U2") (pin "42") (pinfunction "GPIO1_42") (pintype "bidirectional"))
    )
    (net (code "123") (name "unconnected-(U2-GPIO2-Pad44)") (class "Default")
      (node (ref "U2") (pin "44") (pinfunction "GPIO2_44") (pintype "bidirectional"))
    )
    (net (code "124") (name "unconnected-(U2-GPIO3-Pad45)") (class "Default")
      (node (ref "U2") (pin "45") (pinfunction "GPIO3_45") (pintype "bidirectional"))
    )
    (net (code "125") (name "unconnected-(U2-GPIO4-Pad46)") (class "Default")
      (node (ref "U2") (pin "46") (pinfunction "GPIO4_46") (pintype "bidirectional"))
    )
    (net (code "126") (name "unconnected-(U2-NC-Pad27)") (class "Default")
      (node (ref "U2") (pin "27") (pinfunction "NC_27") (pintype "no_connect"))
    )
    (net (code "127") (name "unconnected-(U2-NC-Pad29)") (class "Default")
      (node (ref "U2") (pin "29") (pinfunction "NC_29") (pintype "no_connect"))
    )
    (net (code "128") (name "unconnected-(U6-~{FAULT}-Pad4)") (class "Default")
      (node (ref "U6") (pin "4") (pinfunction "~{FAULT}_4") (pintype "output"))
    )
    (net (code "129") (name "unconnected-(X1-E{slash}D-Pad1)") (class "Default")
      (node (ref "X1") (pin "1") (pinfunction "E/D_1") (pintype "input"))
    )
  )
)
